# BT60.net
KiCad netlist of a schematic drawn in EAGLE
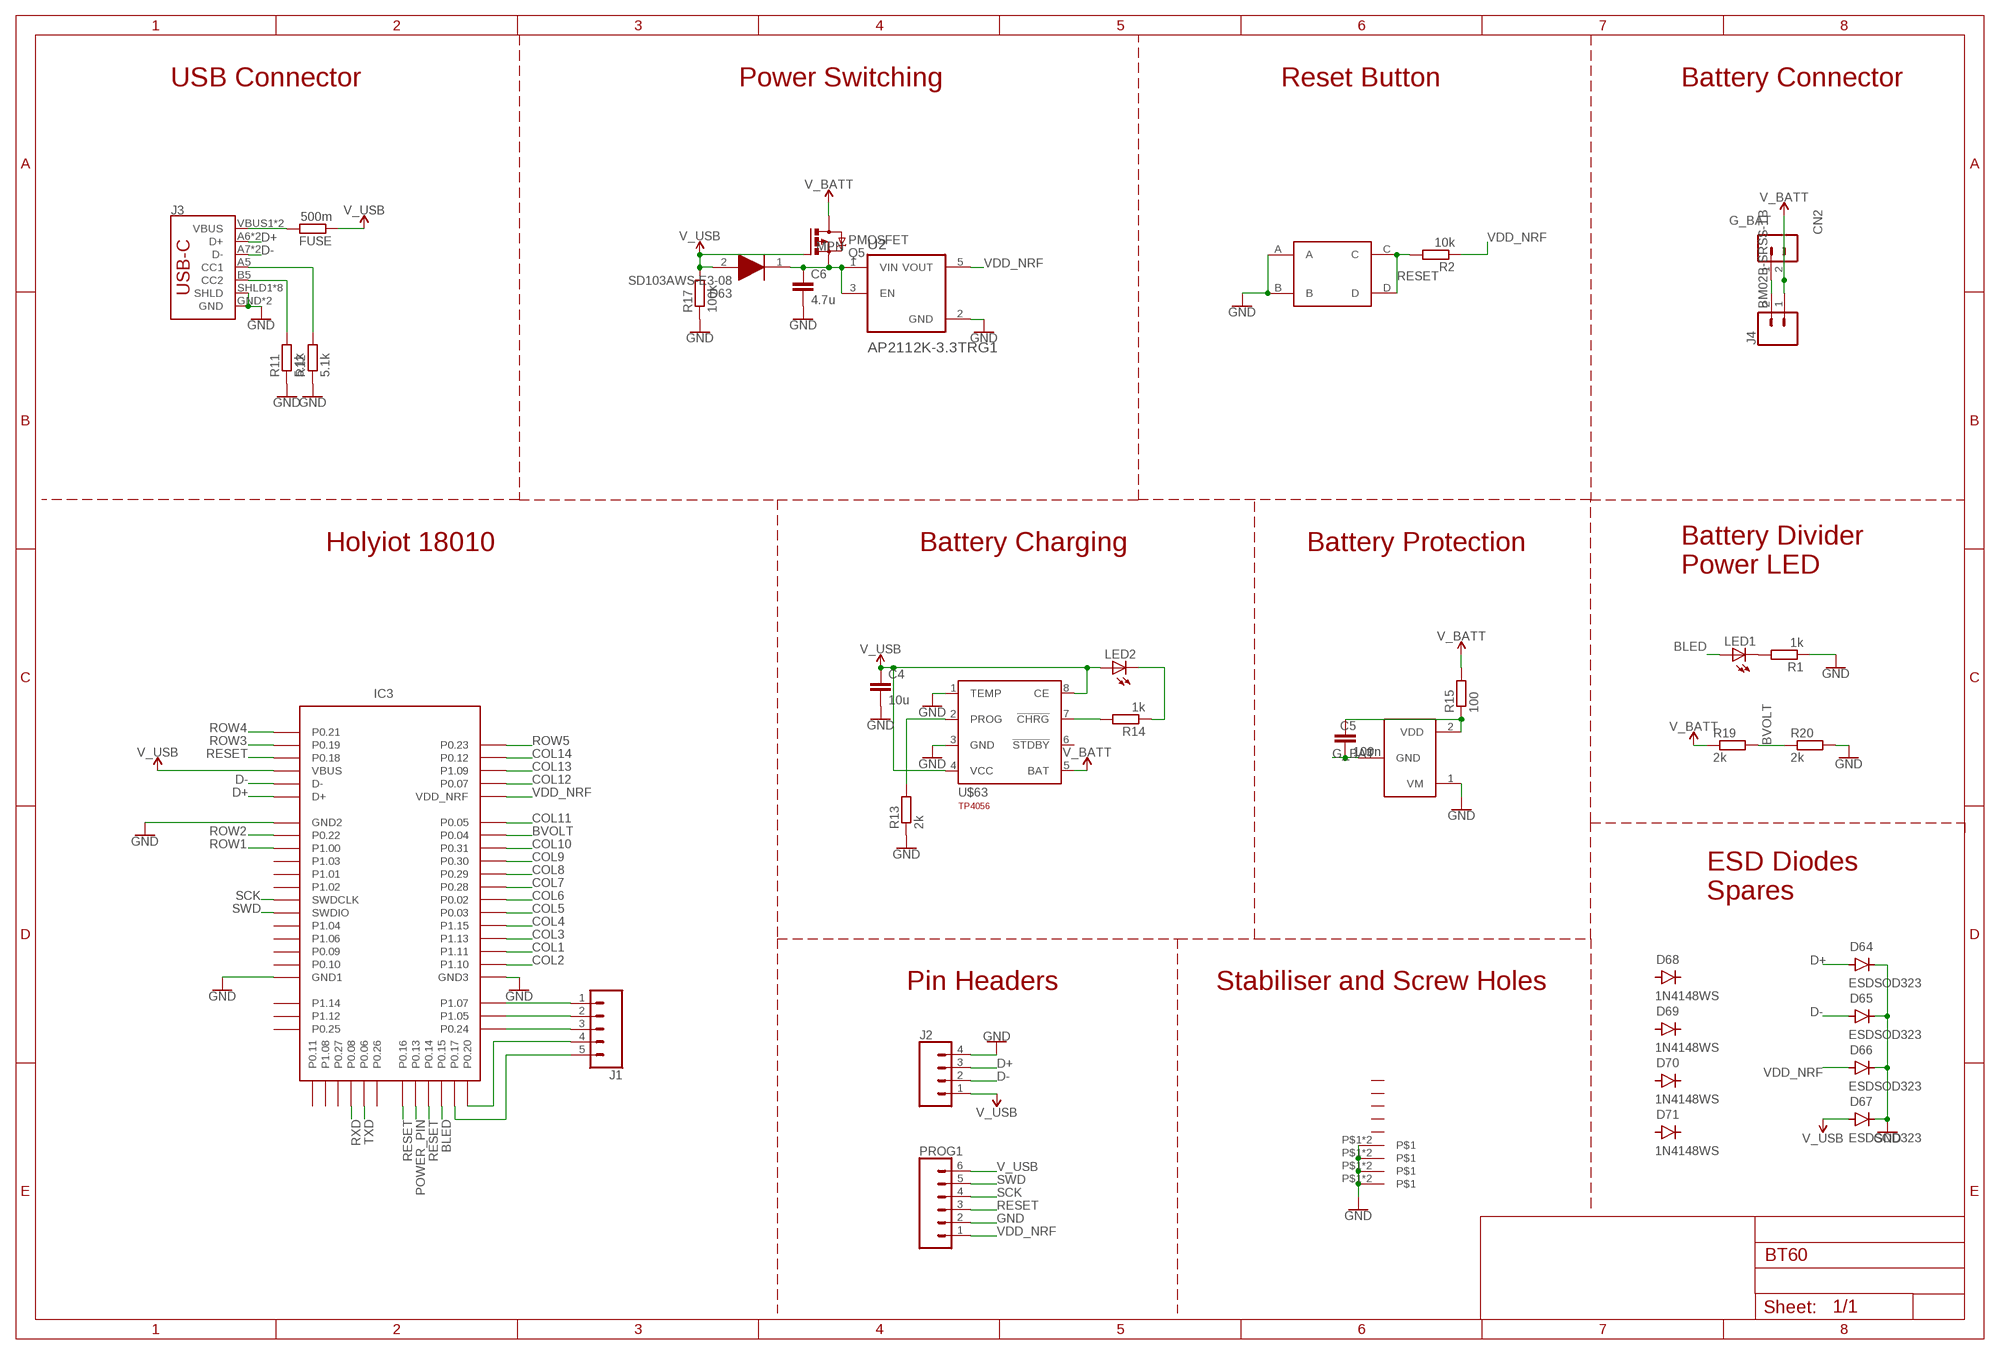
[diagram p0: schematic, sheet 1, part 1 of 2]
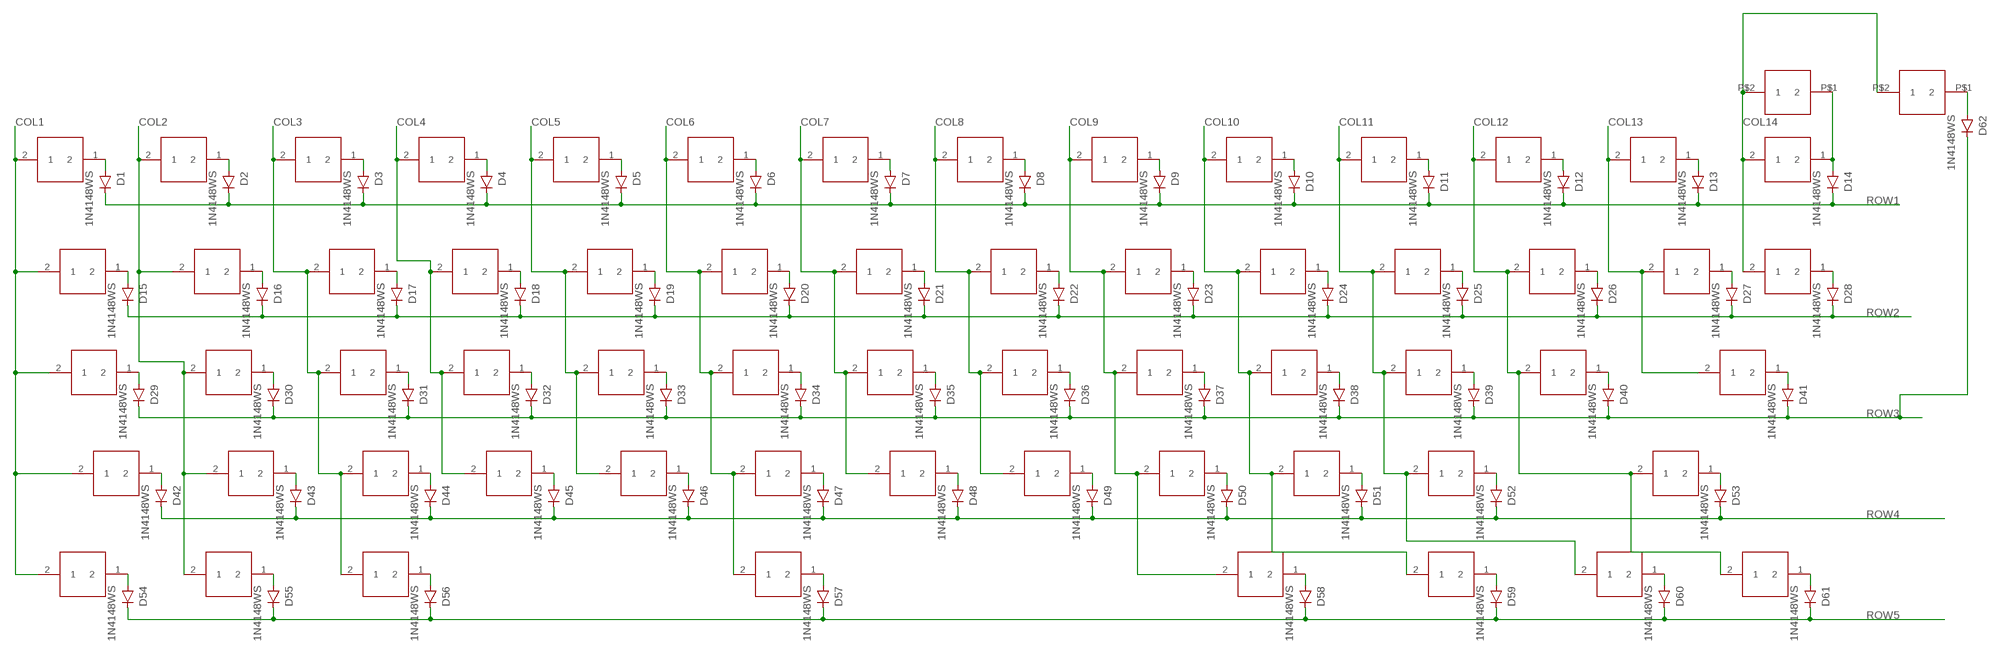
[diagram p1: schematic, sheet 1, part 2 of 2]

(export (version "E")
  (design (tool "Eeschema 10.0.6"))
  (components
    (comp (ref "C4")
      (value "10u")
      (footprint "eagle-import:C0603")
      (libsource (lib "eagle-import") (part "C-EUC0603"))
    )
    (comp (ref "C5")
      (value "100n")
      (footprint "eagle-import:C0603")
      (libsource (lib "eagle-import") (part "C-EUC0603"))
    )
    (comp (ref "C6")
      (value "4.7u")
      (footprint "eagle-import:C0603")
      (libsource (lib "eagle-import") (part "C-EUC0603"))
    )
    (comp (ref "CN2")
      (value "BM02B-SRSS-TB")
      (footprint "eagle-import:BM02B-SRSS-TB")
      (libsource (lib "eagle-import") (part "BM02B-SRSS-TB"))
    )
    (comp (ref "D1")
      (value "1N4148WS")
      (footprint "eagle-import:SOD-323")
      (fields
        (field (name "DIGIKEY_PART_NUMBER") "1N4148WSFSTR-ND")
        (field (name "MANUFACTURER") "Diodes Incorporated")
        (field (name "CREATED_BY") "PCBLayout.com")
      )
      (libsource (lib "eagle-import") (part "1N4148WS"))
    )
    (comp (ref "D2")
      (value "1N4148WS")
      (footprint "eagle-import:SOD-323")
      (fields
        (field (name "DIGIKEY_PART_NUMBER") "1N4148WSFSTR-ND")
        (field (name "MANUFACTURER") "Diodes Incorporated")
        (field (name "CREATED_BY") "PCBLayout.com")
      )
      (libsource (lib "eagle-import") (part "1N4148WS"))
    )
    (comp (ref "D3")
      (value "1N4148WS")
      (footprint "eagle-import:SOD-323")
      (fields
        (field (name "DIGIKEY_PART_NUMBER") "1N4148WSFSTR-ND")
        (field (name "MANUFACTURER") "Diodes Incorporated")
        (field (name "CREATED_BY") "PCBLayout.com")
      )
      (libsource (lib "eagle-import") (part "1N4148WS"))
    )
    (comp (ref "D4")
      (value "1N4148WS")
      (footprint "eagle-import:SOD-323")
      (fields
        (field (name "DIGIKEY_PART_NUMBER") "1N4148WSFSTR-ND")
        (field (name "MANUFACTURER") "Diodes Incorporated")
        (field (name "CREATED_BY") "PCBLayout.com")
      )
      (libsource (lib "eagle-import") (part "1N4148WS"))
    )
    (comp (ref "D5")
      (value "1N4148WS")
      (footprint "eagle-import:SOD-323")
      (fields
        (field (name "DIGIKEY_PART_NUMBER") "1N4148WSFSTR-ND")
        (field (name "MANUFACTURER") "Diodes Incorporated")
        (field (name "CREATED_BY") "PCBLayout.com")
      )
      (libsource (lib "eagle-import") (part "1N4148WS"))
    )
    (comp (ref "D6")
      (value "1N4148WS")
      (footprint "eagle-import:SOD-323")
      (fields
        (field (name "DIGIKEY_PART_NUMBER") "1N4148WSFSTR-ND")
        (field (name "MANUFACTURER") "Diodes Incorporated")
        (field (name "CREATED_BY") "PCBLayout.com")
      )
      (libsource (lib "eagle-import") (part "1N4148WS"))
    )
    (comp (ref "D7")
      (value "1N4148WS")
      (footprint "eagle-import:SOD-323")
      (fields
        (field (name "DIGIKEY_PART_NUMBER") "1N4148WSFSTR-ND")
        (field (name "MANUFACTURER") "Diodes Incorporated")
        (field (name "CREATED_BY") "PCBLayout.com")
      )
      (libsource (lib "eagle-import") (part "1N4148WS"))
    )
    (comp (ref "D8")
      (value "1N4148WS")
      (footprint "eagle-import:SOD-323")
      (fields
        (field (name "DIGIKEY_PART_NUMBER") "1N4148WSFSTR-ND")
        (field (name "MANUFACTURER") "Diodes Incorporated")
        (field (name "CREATED_BY") "PCBLayout.com")
      )
      (libsource (lib "eagle-import") (part "1N4148WS"))
    )
    (comp (ref "D9")
      (value "1N4148WS")
      (footprint "eagle-import:SOD-323")
      (fields
        (field (name "DIGIKEY_PART_NUMBER") "1N4148WSFSTR-ND")
        (field (name "MANUFACTURER") "Diodes Incorporated")
        (field (name "CREATED_BY") "PCBLayout.com")
      )
      (libsource (lib "eagle-import") (part "1N4148WS"))
    )
    (comp (ref "D10")
      (value "1N4148WS")
      (footprint "eagle-import:SOD-323")
      (fields
        (field (name "DIGIKEY_PART_NUMBER") "1N4148WSFSTR-ND")
        (field (name "MANUFACTURER") "Diodes Incorporated")
        (field (name "CREATED_BY") "PCBLayout.com")
      )
      (libsource (lib "eagle-import") (part "1N4148WS"))
    )
    (comp (ref "D11")
      (value "1N4148WS")
      (footprint "eagle-import:SOD-323")
      (fields
        (field (name "DIGIKEY_PART_NUMBER") "1N4148WSFSTR-ND")
        (field (name "MANUFACTURER") "Diodes Incorporated")
        (field (name "CREATED_BY") "PCBLayout.com")
      )
      (libsource (lib "eagle-import") (part "1N4148WS"))
    )
    (comp (ref "D12")
      (value "1N4148WS")
      (footprint "eagle-import:SOD-323")
      (fields
        (field (name "DIGIKEY_PART_NUMBER") "1N4148WSFSTR-ND")
        (field (name "MANUFACTURER") "Diodes Incorporated")
        (field (name "CREATED_BY") "PCBLayout.com")
      )
      (libsource (lib "eagle-import") (part "1N4148WS"))
    )
    (comp (ref "D13")
      (value "1N4148WS")
      (footprint "eagle-import:SOD-323")
      (fields
        (field (name "DIGIKEY_PART_NUMBER") "1N4148WSFSTR-ND")
        (field (name "MANUFACTURER") "Diodes Incorporated")
        (field (name "CREATED_BY") "PCBLayout.com")
      )
      (libsource (lib "eagle-import") (part "1N4148WS"))
    )
    (comp (ref "D14")
      (value "1N4148WS")
      (footprint "eagle-import:SOD-323")
      (fields
        (field (name "DIGIKEY_PART_NUMBER") "1N4148WSFSTR-ND")
        (field (name "MANUFACTURER") "Diodes Incorporated")
        (field (name "CREATED_BY") "PCBLayout.com")
      )
      (libsource (lib "eagle-import") (part "1N4148WS"))
    )
    (comp (ref "D15")
      (value "1N4148WS")
      (footprint "eagle-import:SOD-323")
      (fields
        (field (name "DIGIKEY_PART_NUMBER") "1N4148WSFSTR-ND")
        (field (name "MANUFACTURER") "Diodes Incorporated")
        (field (name "CREATED_BY") "PCBLayout.com")
      )
      (libsource (lib "eagle-import") (part "1N4148WS"))
    )
    (comp (ref "D16")
      (value "1N4148WS")
      (footprint "eagle-import:SOD-323")
      (fields
        (field (name "DIGIKEY_PART_NUMBER") "1N4148WSFSTR-ND")
        (field (name "MANUFACTURER") "Diodes Incorporated")
        (field (name "CREATED_BY") "PCBLayout.com")
      )
      (libsource (lib "eagle-import") (part "1N4148WS"))
    )
    (comp (ref "D17")
      (value "1N4148WS")
      (footprint "eagle-import:SOD-323")
      (fields
        (field (name "DIGIKEY_PART_NUMBER") "1N4148WSFSTR-ND")
        (field (name "MANUFACTURER") "Diodes Incorporated")
        (field (name "CREATED_BY") "PCBLayout.com")
      )
      (libsource (lib "eagle-import") (part "1N4148WS"))
    )
    (comp (ref "D18")
      (value "1N4148WS")
      (footprint "eagle-import:SOD-323")
      (fields
        (field (name "DIGIKEY_PART_NUMBER") "1N4148WSFSTR-ND")
        (field (name "MANUFACTURER") "Diodes Incorporated")
        (field (name "CREATED_BY") "PCBLayout.com")
      )
      (libsource (lib "eagle-import") (part "1N4148WS"))
    )
    (comp (ref "D19")
      (value "1N4148WS")
      (footprint "eagle-import:SOD-323")
      (fields
        (field (name "DIGIKEY_PART_NUMBER") "1N4148WSFSTR-ND")
        (field (name "MANUFACTURER") "Diodes Incorporated")
        (field (name "CREATED_BY") "PCBLayout.com")
      )
      (libsource (lib "eagle-import") (part "1N4148WS"))
    )
    (comp (ref "D20")
      (value "1N4148WS")
      (footprint "eagle-import:SOD-323")
      (fields
        (field (name "DIGIKEY_PART_NUMBER") "1N4148WSFSTR-ND")
        (field (name "MANUFACTURER") "Diodes Incorporated")
        (field (name "CREATED_BY") "PCBLayout.com")
      )
      (libsource (lib "eagle-import") (part "1N4148WS"))
    )
    (comp (ref "D21")
      (value "1N4148WS")
      (footprint "eagle-import:SOD-323")
      (fields
        (field (name "DIGIKEY_PART_NUMBER") "1N4148WSFSTR-ND")
        (field (name "MANUFACTURER") "Diodes Incorporated")
        (field (name "CREATED_BY") "PCBLayout.com")
      )
      (libsource (lib "eagle-import") (part "1N4148WS"))
    )
    (comp (ref "D22")
      (value "1N4148WS")
      (footprint "eagle-import:SOD-323")
      (fields
        (field (name "DIGIKEY_PART_NUMBER") "1N4148WSFSTR-ND")
        (field (name "MANUFACTURER") "Diodes Incorporated")
        (field (name "CREATED_BY") "PCBLayout.com")
      )
      (libsource (lib "eagle-import") (part "1N4148WS"))
    )
    (comp (ref "D23")
      (value "1N4148WS")
      (footprint "eagle-import:SOD-323")
      (fields
        (field (name "DIGIKEY_PART_NUMBER") "1N4148WSFSTR-ND")
        (field (name "MANUFACTURER") "Diodes Incorporated")
        (field (name "CREATED_BY") "PCBLayout.com")
      )
      (libsource (lib "eagle-import") (part "1N4148WS"))
    )
    (comp (ref "D24")
      (value "1N4148WS")
      (footprint "eagle-import:SOD-323")
      (fields
        (field (name "DIGIKEY_PART_NUMBER") "1N4148WSFSTR-ND")
        (field (name "MANUFACTURER") "Diodes Incorporated")
        (field (name "CREATED_BY") "PCBLayout.com")
      )
      (libsource (lib "eagle-import") (part "1N4148WS"))
    )
    (comp (ref "D25")
      (value "1N4148WS")
      (footprint "eagle-import:SOD-323")
      (fields
        (field (name "DIGIKEY_PART_NUMBER") "1N4148WSFSTR-ND")
        (field (name "MANUFACTURER") "Diodes Incorporated")
        (field (name "CREATED_BY") "PCBLayout.com")
      )
      (libsource (lib "eagle-import") (part "1N4148WS"))
    )
    (comp (ref "D26")
      (value "1N4148WS")
      (footprint "eagle-import:SOD-323")
      (fields
        (field (name "DIGIKEY_PART_NUMBER") "1N4148WSFSTR-ND")
        (field (name "MANUFACTURER") "Diodes Incorporated")
        (field (name "CREATED_BY") "PCBLayout.com")
      )
      (libsource (lib "eagle-import") (part "1N4148WS"))
    )
    (comp (ref "D27")
      (value "1N4148WS")
      (footprint "eagle-import:SOD-323")
      (fields
        (field (name "DIGIKEY_PART_NUMBER") "1N4148WSFSTR-ND")
        (field (name "MANUFACTURER") "Diodes Incorporated")
        (field (name "CREATED_BY") "PCBLayout.com")
      )
      (libsource (lib "eagle-import") (part "1N4148WS"))
    )
    (comp (ref "D28")
      (value "1N4148WS")
      (footprint "eagle-import:SOD-323")
      (fields
        (field (name "DIGIKEY_PART_NUMBER") "1N4148WSFSTR-ND")
        (field (name "MANUFACTURER") "Diodes Incorporated")
        (field (name "CREATED_BY") "PCBLayout.com")
      )
      (libsource (lib "eagle-import") (part "1N4148WS"))
    )
    (comp (ref "D29")
      (value "1N4148WS")
      (footprint "eagle-import:SOD-323")
      (fields
        (field (name "DIGIKEY_PART_NUMBER") "1N4148WSFSTR-ND")
        (field (name "MANUFACTURER") "Diodes Incorporated")
        (field (name "CREATED_BY") "PCBLayout.com")
      )
      (libsource (lib "eagle-import") (part "1N4148WS"))
    )
    (comp (ref "D30")
      (value "1N4148WS")
      (footprint "eagle-import:SOD-323")
      (fields
        (field (name "DIGIKEY_PART_NUMBER") "1N4148WSFSTR-ND")
        (field (name "MANUFACTURER") "Diodes Incorporated")
        (field (name "CREATED_BY") "PCBLayout.com")
      )
      (libsource (lib "eagle-import") (part "1N4148WS"))
    )
    (comp (ref "D31")
      (value "1N4148WS")
      (footprint "eagle-import:SOD-323")
      (fields
        (field (name "DIGIKEY_PART_NUMBER") "1N4148WSFSTR-ND")
        (field (name "MANUFACTURER") "Diodes Incorporated")
        (field (name "CREATED_BY") "PCBLayout.com")
      )
      (libsource (lib "eagle-import") (part "1N4148WS"))
    )
    (comp (ref "D32")
      (value "1N4148WS")
      (footprint "eagle-import:SOD-323")
      (fields
        (field (name "DIGIKEY_PART_NUMBER") "1N4148WSFSTR-ND")
        (field (name "MANUFACTURER") "Diodes Incorporated")
        (field (name "CREATED_BY") "PCBLayout.com")
      )
      (libsource (lib "eagle-import") (part "1N4148WS"))
    )
    (comp (ref "D33")
      (value "1N4148WS")
      (footprint "eagle-import:SOD-323")
      (fields
        (field (name "DIGIKEY_PART_NUMBER") "1N4148WSFSTR-ND")
        (field (name "MANUFACTURER") "Diodes Incorporated")
        (field (name "CREATED_BY") "PCBLayout.com")
      )
      (libsource (lib "eagle-import") (part "1N4148WS"))
    )
    (comp (ref "D34")
      (value "1N4148WS")
      (footprint "eagle-import:SOD-323")
      (fields
        (field (name "DIGIKEY_PART_NUMBER") "1N4148WSFSTR-ND")
        (field (name "MANUFACTURER") "Diodes Incorporated")
        (field (name "CREATED_BY") "PCBLayout.com")
      )
      (libsource (lib "eagle-import") (part "1N4148WS"))
    )
    (comp (ref "D35")
      (value "1N4148WS")
      (footprint "eagle-import:SOD-323")
      (fields
        (field (name "DIGIKEY_PART_NUMBER") "1N4148WSFSTR-ND")
        (field (name "MANUFACTURER") "Diodes Incorporated")
        (field (name "CREATED_BY") "PCBLayout.com")
      )
      (libsource (lib "eagle-import") (part "1N4148WS"))
    )
    (comp (ref "D36")
      (value "1N4148WS")
      (footprint "eagle-import:SOD-323")
      (fields
        (field (name "DIGIKEY_PART_NUMBER") "1N4148WSFSTR-ND")
        (field (name "MANUFACTURER") "Diodes Incorporated")
        (field (name "CREATED_BY") "PCBLayout.com")
      )
      (libsource (lib "eagle-import") (part "1N4148WS"))
    )
    (comp (ref "D37")
      (value "1N4148WS")
      (footprint "eagle-import:SOD-323")
      (fields
        (field (name "DIGIKEY_PART_NUMBER") "1N4148WSFSTR-ND")
        (field (name "MANUFACTURER") "Diodes Incorporated")
        (field (name "CREATED_BY") "PCBLayout.com")
      )
      (libsource (lib "eagle-import") (part "1N4148WS"))
    )
    (comp (ref "D38")
      (value "1N4148WS")
      (footprint "eagle-import:SOD-323")
      (fields
        (field (name "DIGIKEY_PART_NUMBER") "1N4148WSFSTR-ND")
        (field (name "MANUFACTURER") "Diodes Incorporated")
        (field (name "CREATED_BY") "PCBLayout.com")
      )
      (libsource (lib "eagle-import") (part "1N4148WS"))
    )
    (comp (ref "D39")
      (value "1N4148WS")
      (footprint "eagle-import:SOD-323")
      (fields
        (field (name "DIGIKEY_PART_NUMBER") "1N4148WSFSTR-ND")
        (field (name "MANUFACTURER") "Diodes Incorporated")
        (field (name "CREATED_BY") "PCBLayout.com")
      )
      (libsource (lib "eagle-import") (part "1N4148WS"))
    )
    (comp (ref "D40")
      (value "1N4148WS")
      (footprint "eagle-import:SOD-323")
      (fields
        (field (name "DIGIKEY_PART_NUMBER") "1N4148WSFSTR-ND")
        (field (name "MANUFACTURER") "Diodes Incorporated")
        (field (name "CREATED_BY") "PCBLayout.com")
      )
      (libsource (lib "eagle-import") (part "1N4148WS"))
    )
    (comp (ref "D41")
      (value "1N4148WS")
      (footprint "eagle-import:SOD-323")
      (fields
        (field (name "DIGIKEY_PART_NUMBER") "1N4148WSFSTR-ND")
        (field (name "MANUFACTURER") "Diodes Incorporated")
        (field (name "CREATED_BY") "PCBLayout.com")
      )
      (libsource (lib "eagle-import") (part "1N4148WS"))
    )
    (comp (ref "D42")
      (value "1N4148WS")
      (footprint "eagle-import:SOD-323")
      (fields
        (field (name "DIGIKEY_PART_NUMBER") "1N4148WSFSTR-ND")
        (field (name "MANUFACTURER") "Diodes Incorporated")
        (field (name "CREATED_BY") "PCBLayout.com")
      )
      (libsource (lib "eagle-import") (part "1N4148WS"))
    )
    (comp (ref "D43")
      (value "1N4148WS")
      (footprint "eagle-import:SOD-323")
      (fields
        (field (name "DIGIKEY_PART_NUMBER") "1N4148WSFSTR-ND")
        (field (name "MANUFACTURER") "Diodes Incorporated")
        (field (name "CREATED_BY") "PCBLayout.com")
      )
      (libsource (lib "eagle-import") (part "1N4148WS"))
    )
    (comp (ref "D44")
      (value "1N4148WS")
      (footprint "eagle-import:SOD-323")
      (fields
        (field (name "DIGIKEY_PART_NUMBER") "1N4148WSFSTR-ND")
        (field (name "MANUFACTURER") "Diodes Incorporated")
        (field (name "CREATED_BY") "PCBLayout.com")
      )
      (libsource (lib "eagle-import") (part "1N4148WS"))
    )
    (comp (ref "D45")
      (value "1N4148WS")
      (footprint "eagle-import:SOD-323")
      (fields
        (field (name "DIGIKEY_PART_NUMBER") "1N4148WSFSTR-ND")
        (field (name "MANUFACTURER") "Diodes Incorporated")
        (field (name "CREATED_BY") "PCBLayout.com")
      )
      (libsource (lib "eagle-import") (part "1N4148WS"))
    )
    (comp (ref "D46")
      (value "1N4148WS")
      (footprint "eagle-import:SOD-323")
      (fields
        (field (name "DIGIKEY_PART_NUMBER") "1N4148WSFSTR-ND")
        (field (name "MANUFACTURER") "Diodes Incorporated")
        (field (name "CREATED_BY") "PCBLayout.com")
      )
      (libsource (lib "eagle-import") (part "1N4148WS"))
    )
    (comp (ref "D47")
      (value "1N4148WS")
      (footprint "eagle-import:SOD-323")
      (fields
        (field (name "DIGIKEY_PART_NUMBER") "1N4148WSFSTR-ND")
        (field (name "MANUFACTURER") "Diodes Incorporated")
        (field (name "CREATED_BY") "PCBLayout.com")
      )
      (libsource (lib "eagle-import") (part "1N4148WS"))
    )
    (comp (ref "D48")
      (value "1N4148WS")
      (footprint "eagle-import:SOD-323")
      (fields
        (field (name "DIGIKEY_PART_NUMBER") "1N4148WSFSTR-ND")
        (field (name "MANUFACTURER") "Diodes Incorporated")
        (field (name "CREATED_BY") "PCBLayout.com")
      )
      (libsource (lib "eagle-import") (part "1N4148WS"))
    )
    (comp (ref "D49")
      (value "1N4148WS")
      (footprint "eagle-import:SOD-323")
      (fields
        (field (name "DIGIKEY_PART_NUMBER") "1N4148WSFSTR-ND")
        (field (name "MANUFACTURER") "Diodes Incorporated")
        (field (name "CREATED_BY") "PCBLayout.com")
      )
      (libsource (lib "eagle-import") (part "1N4148WS"))
    )
    (comp (ref "D50")
      (value "1N4148WS")
      (footprint "eagle-import:SOD-323")
      (fields
        (field (name "DIGIKEY_PART_NUMBER") "1N4148WSFSTR-ND")
        (field (name "MANUFACTURER") "Diodes Incorporated")
        (field (name "CREATED_BY") "PCBLayout.com")
      )
      (libsource (lib "eagle-import") (part "1N4148WS"))
    )
    (comp (ref "D51")
      (value "1N4148WS")
      (footprint "eagle-import:SOD-323")
      (fields
        (field (name "DIGIKEY_PART_NUMBER") "1N4148WSFSTR-ND")
        (field (name "MANUFACTURER") "Diodes Incorporated")
        (field (name "CREATED_BY") "PCBLayout.com")
      )
      (libsource (lib "eagle-import") (part "1N4148WS"))
    )
    (comp (ref "D52")
      (value "1N4148WS")
      (footprint "eagle-import:SOD-323")
      (fields
        (field (name "DIGIKEY_PART_NUMBER") "1N4148WSFSTR-ND")
        (field (name "MANUFACTURER") "Diodes Incorporated")
        (field (name "CREATED_BY") "PCBLayout.com")
      )
      (libsource (lib "eagle-import") (part "1N4148WS"))
    )
    (comp (ref "D53")
      (value "1N4148WS")
      (footprint "eagle-import:SOD-323")
      (fields
        (field (name "DIGIKEY_PART_NUMBER") "1N4148WSFSTR-ND")
        (field (name "MANUFACTURER") "Diodes Incorporated")
        (field (name "CREATED_BY") "PCBLayout.com")
      )
      (libsource (lib "eagle-import") (part "1N4148WS"))
    )
    (comp (ref "D54")
      (value "1N4148WS")
      (footprint "eagle-import:SOD-323")
      (fields
        (field (name "DIGIKEY_PART_NUMBER") "1N4148WSFSTR-ND")
        (field (name "MANUFACTURER") "Diodes Incorporated")
        (field (name "CREATED_BY") "PCBLayout.com")
      )
      (libsource (lib "eagle-import") (part "1N4148WS"))
    )
    (comp (ref "D55")
      (value "1N4148WS")
      (footprint "eagle-import:SOD-323")
      (fields
        (field (name "DIGIKEY_PART_NUMBER") "1N4148WSFSTR-ND")
        (field (name "MANUFACTURER") "Diodes Incorporated")
        (field (name "CREATED_BY") "PCBLayout.com")
      )
      (libsource (lib "eagle-import") (part "1N4148WS"))
    )
    (comp (ref "D56")
      (value "1N4148WS")
      (footprint "eagle-import:SOD-323")
      (fields
        (field (name "DIGIKEY_PART_NUMBER") "1N4148WSFSTR-ND")
        (field (name "MANUFACTURER") "Diodes Incorporated")
        (field (name "CREATED_BY") "PCBLayout.com")
      )
      (libsource (lib "eagle-import") (part "1N4148WS"))
    )
    (comp (ref "D57")
      (value "1N4148WS")
      (footprint "eagle-import:SOD-323")
      (fields
        (field (name "DIGIKEY_PART_NUMBER") "1N4148WSFSTR-ND")
        (field (name "MANUFACTURER") "Diodes Incorporated")
        (field (name "CREATED_BY") "PCBLayout.com")
      )
      (libsource (lib "eagle-import") (part "1N4148WS"))
    )
    (comp (ref "D58")
      (value "1N4148WS")
      (footprint "eagle-import:SOD-323")
      (fields
        (field (name "DIGIKEY_PART_NUMBER") "1N4148WSFSTR-ND")
        (field (name "MANUFACTURER") "Diodes Incorporated")
        (field (name "CREATED_BY") "PCBLayout.com")
      )
      (libsource (lib "eagle-import") (part "1N4148WS"))
    )
    (comp (ref "D59")
      (value "1N4148WS")
      (footprint "eagle-import:SOD-323")
      (fields
        (field (name "DIGIKEY_PART_NUMBER") "1N4148WSFSTR-ND")
        (field (name "MANUFACTURER") "Diodes Incorporated")
        (field (name "CREATED_BY") "PCBLayout.com")
      )
      (libsource (lib "eagle-import") (part "1N4148WS"))
    )
    (comp (ref "D60")
      (value "1N4148WS")
      (footprint "eagle-import:SOD-323")
      (fields
        (field (name "DIGIKEY_PART_NUMBER") "1N4148WSFSTR-ND")
        (field (name "MANUFACTURER") "Diodes Incorporated")
        (field (name "CREATED_BY") "PCBLayout.com")
      )
      (libsource (lib "eagle-import") (part "1N4148WS"))
    )
    (comp (ref "D61")
      (value "1N4148WS")
      (footprint "eagle-import:SOD-323")
      (fields
        (field (name "DIGIKEY_PART_NUMBER") "1N4148WSFSTR-ND")
        (field (name "MANUFACTURER") "Diodes Incorporated")
        (field (name "CREATED_BY") "PCBLayout.com")
      )
      (libsource (lib "eagle-import") (part "1N4148WS"))
    )
    (comp (ref "D62")
      (value "1N4148WS")
      (footprint "eagle-import:SOD-323")
      (fields
        (field (name "DIGIKEY_PART_NUMBER") "1N4148WSFSTR-ND")
        (field (name "MANUFACTURER") "Diodes Incorporated")
        (field (name "CREATED_BY") "PCBLayout.com")
      )
      (libsource (lib "eagle-import") (part "1N4148WS"))
    )
    (comp (ref "D63")
      (value "SD103AWS-E3-08")
      (footprint "eagle-import:SOD2713X115N")
      (fields (field (name "MOUSER_PART_NUMBER") "78-SD103AWS-E3-08"))
      (libsource (lib "eagle-import") (part "SD103AWS-E3-08"))
    )
    (comp (ref "D64")
      (value "ESDSOD323")
      (footprint "eagle-import:SOD-323")
      (fields (field (name "MANUFACTURER") "Diodes Incorporated") (field (name "CREATED_BY") "PCBLayout.com"))
      (libsource (lib "eagle-import") (part "ESDSOD323"))
    )
    (comp (ref "D65")
      (value "ESDSOD323")
      (footprint "eagle-import:SOD-323")
      (fields (field (name "MANUFACTURER") "Diodes Incorporated") (field (name "CREATED_BY") "PCBLayout.com"))
      (libsource (lib "eagle-import") (part "ESDSOD323"))
    )
    (comp (ref "D66")
      (value "ESDSOD323")
      (footprint "eagle-import:SOD-323")
      (fields (field (name "MANUFACTURER") "Diodes Incorporated") (field (name "CREATED_BY") "PCBLayout.com"))
      (libsource (lib "eagle-import") (part "ESDSOD323"))
    )
    (comp (ref "D67")
      (value "ESDSOD323")
      (footprint "eagle-import:SOD-323")
      (fields (field (name "MANUFACTURER") "Diodes Incorporated") (field (name "CREATED_BY") "PCBLayout.com"))
      (libsource (lib "eagle-import") (part "ESDSOD323"))
    )
    (comp (ref "D68")
      (value "1N4148WS")
      (footprint "eagle-import:SOD-323")
      (fields
        (field (name "DIGIKEY_PART_NUMBER") "1N4148WSFSTR-ND")
        (field (name "MANUFACTURER") "Diodes Incorporated")
        (field (name "CREATED_BY") "PCBLayout.com")
      )
      (libsource (lib "eagle-import") (part "1N4148WS"))
    )
    (comp (ref "D69")
      (value "1N4148WS")
      (footprint "eagle-import:SOD-323")
      (fields
        (field (name "DIGIKEY_PART_NUMBER") "1N4148WSFSTR-ND")
        (field (name "MANUFACTURER") "Diodes Incorporated")
        (field (name "CREATED_BY") "PCBLayout.com")
      )
      (libsource (lib "eagle-import") (part "1N4148WS"))
    )
    (comp (ref "D70")
      (value "1N4148WS")
      (footprint "eagle-import:SOD-323")
      (fields
        (field (name "DIGIKEY_PART_NUMBER") "1N4148WSFSTR-ND")
        (field (name "MANUFACTURER") "Diodes Incorporated")
        (field (name "CREATED_BY") "PCBLayout.com")
      )
      (libsource (lib "eagle-import") (part "1N4148WS"))
    )
    (comp (ref "D71")
      (value "1N4148WS")
      (footprint "eagle-import:SOD-323")
      (fields
        (field (name "DIGIKEY_PART_NUMBER") "1N4148WSFSTR-ND")
        (field (name "MANUFACTURER") "Diodes Incorporated")
        (field (name "CREATED_BY") "PCBLayout.com")
      )
      (libsource (lib "eagle-import") (part "1N4148WS"))
    )
    (comp (ref "FUSE")
      (value "500m")
      (footprint "eagle-import:R0603")
      (libsource (lib "eagle-import") (part "R-EU_R0603"))
    )
    (comp (ref "IC1")
      (value "XB3303ASOT23")
      (footprint "eagle-import:SOT23-3")
      (libsource (lib "eagle-import") (part "XB3303ASOT23"))
    )
    (comp (ref "IC3")
      (value "HOLYIOT_18010")
      (footprint "eagle-import:PCBCOMPONENT_1")
      (libsource (lib "eagle-import") (part "HOLYIOT_18010"))
    )
    (comp (ref "J1")
      (value "CONN_051.27MM")
      (footprint "eagle-import:1X05_1.27MM")
      (libsource (lib "eagle-import") (part "CONN_051.27MM"))
    )
    (comp (ref "J2")
      (value "CONN_041X04_NO_SILK")
      (footprint "eagle-import:1X04_NO_SILK")
      (libsource (lib "eagle-import") (part "CONN_041X04_NO_SILK"))
    )
    (comp (ref "J3")
      (value "SPARKFUN-CONNECTORS_USB_C16PIN")
      (footprint "eagle-import:SPARKFUN-CONNECTORS_USB-C-16P")
      (libsource (lib "eagle-import") (part "SPARKFUN-CONNECTORS_USB_C16PIN"))
    )
    (comp (ref "J4")
      (value "CONN_02")
      (footprint "eagle-import:1X02")
      (libsource (lib "eagle-import") (part "CONN_02"))
    )
    (comp (ref "LED1")
      (value "LEDCHIPLED_0805")
      (footprint "eagle-import:CHIPLED_0805")
      (libsource (lib "eagle-import") (part "LEDCHIPLED_0805"))
    )
    (comp (ref "LED2")
      (value "LEDCHIPLED_0805")
      (footprint "eagle-import:CHIPLED_0805")
      (libsource (lib "eagle-import") (part "LEDCHIPLED_0805"))
    )
    (comp (ref "PROG1")
      (value "CONN_06NO_SILK_FEMALE_PTH")
      (footprint "eagle-import:1X06_NO_SILK")
      (libsource (lib "eagle-import") (part "CONN_06NO_SILK_FEMALE_PTH"))
    )
    (comp (ref "Q5")
      (value "PMOSFET")
      (footprint "eagle-import:SOT23")
      (fields (field (name "MPN") "SL2301S"))
      (libsource (lib "eagle-import") (part "PMOSFETSOT23_"))
    )
    (comp (ref "R1")
      (value "1k")
      (footprint "eagle-import:R0603")
      (libsource (lib "eagle-import") (part "R-EU_R0603"))
    )
    (comp (ref "R2")
      (value "10k")
      (footprint "eagle-import:R0603")
      (libsource (lib "eagle-import") (part "R-EU_R0603"))
    )
    (comp (ref "R11")
      (value "5.1k")
      (footprint "eagle-import:R0603")
      (libsource (lib "eagle-import") (part "R-EU_R0603"))
    )
    (comp (ref "R12")
      (value "5.1k")
      (footprint "eagle-import:R0603")
      (libsource (lib "eagle-import") (part "R-EU_R0603"))
    )
    (comp (ref "R13")
      (value "2k")
      (footprint "eagle-import:R0603")
      (libsource (lib "eagle-import") (part "R-EU_R0603"))
    )
    (comp (ref "R14")
      (value "1k")
      (footprint "eagle-import:R0603")
      (libsource (lib "eagle-import") (part "R-EU_R0603"))
    )
    (comp (ref "R15")
      (value "100")
      (footprint "eagle-import:R0603")
      (libsource (lib "eagle-import") (part "R-EU_R0603"))
    )
    (comp (ref "R17")
      (value "100k")
      (footprint "eagle-import:R0603")
      (libsource (lib "eagle-import") (part "R-EU_R0603"))
    )
    (comp (ref "R19")
      (value "2k")
      (footprint "eagle-import:R0603")
      (libsource (lib "eagle-import") (part "R-EU_R0603"))
    )
    (comp (ref "R20")
      (value "2k")
      (footprint "eagle-import:R0603")
      (libsource (lib "eagle-import") (part "R-EU_R0603"))
    )
    (comp (ref "U$1")
      (value "CHERRY")
      (footprint "eagle-import:CHERRY")
      (libsource (lib "eagle-import") (part "CHERRY"))
    )
    (comp (ref "U$2")
      (value "CHERRY")
      (footprint "eagle-import:CHERRY")
      (libsource (lib "eagle-import") (part "CHERRY"))
    )
    (comp (ref "U$3")
      (value "CHERRY")
      (footprint "eagle-import:CHERRY")
      (libsource (lib "eagle-import") (part "CHERRY"))
    )
    (comp (ref "U$4")
      (value "CHERRY")
      (footprint "eagle-import:CHERRY")
      (libsource (lib "eagle-import") (part "CHERRY"))
    )
    (comp (ref "U$5")
      (value "CHERRY")
      (footprint "eagle-import:CHERRY")
      (libsource (lib "eagle-import") (part "CHERRY"))
    )
    (comp (ref "U$6")
      (value "CHERRY")
      (footprint "eagle-import:CHERRY")
      (libsource (lib "eagle-import") (part "CHERRY"))
    )
    (comp (ref "U$7")
      (value "CHERRY")
      (footprint "eagle-import:CHERRY")
      (libsource (lib "eagle-import") (part "CHERRY"))
    )
    (comp (ref "U$8")
      (value "CHERRY")
      (footprint "eagle-import:CHERRY")
      (libsource (lib "eagle-import") (part "CHERRY"))
    )
    (comp (ref "U$9")
      (value "CHERRY")
      (footprint "eagle-import:CHERRY")
      (libsource (lib "eagle-import") (part "CHERRY"))
    )
    (comp (ref "U$10")
      (value "CHERRY")
      (footprint "eagle-import:CHERRY")
      (libsource (lib "eagle-import") (part "CHERRY"))
    )
    (comp (ref "U$11")
      (value "CHERRY")
      (footprint "eagle-import:CHERRY")
      (libsource (lib "eagle-import") (part "CHERRY"))
    )
    (comp (ref "U$12")
      (value "CHERRY")
      (footprint "eagle-import:CHERRY")
      (libsource (lib "eagle-import") (part "CHERRY"))
    )
    (comp (ref "U$13")
      (value "CHERRY")
      (footprint "eagle-import:CHERRY")
      (libsource (lib "eagle-import") (part "CHERRY"))
    )
    (comp (ref "U$14")
      (value "CHERRY_CORNER_OFFED")
      (footprint "eagle-import:CHERRY_CORNER_OFFED")
      (libsource (lib "eagle-import") (part "CHERRY_CORNER_OFFED"))
    )
    (comp (ref "U$15")
      (value "CHERRY")
      (footprint "eagle-import:CHERRY")
      (libsource (lib "eagle-import") (part "CHERRY"))
    )
    (comp (ref "U$16")
      (value "CHERRY")
      (footprint "eagle-import:CHERRY")
      (libsource (lib "eagle-import") (part "CHERRY"))
    )
    (comp (ref "U$17")
      (value "CHERRY")
      (footprint "eagle-import:CHERRY")
      (libsource (lib "eagle-import") (part "CHERRY"))
    )
    (comp (ref "U$18")
      (value "CHERRY")
      (footprint "eagle-import:CHERRY")
      (libsource (lib "eagle-import") (part "CHERRY"))
    )
    (comp (ref "U$19")
      (value "CHERRY")
      (footprint "eagle-import:CHERRY")
      (libsource (lib "eagle-import") (part "CHERRY"))
    )
    (comp (ref "U$20")
      (value "CHERRY")
      (footprint "eagle-import:CHERRY")
      (libsource (lib "eagle-import") (part "CHERRY"))
    )
    (comp (ref "U$21")
      (value "CHERRY")
      (footprint "eagle-import:CHERRY")
      (libsource (lib "eagle-import") (part "CHERRY"))
    )
    (comp (ref "U$22")
      (value "CHERRY")
      (footprint "eagle-import:CHERRY")
      (libsource (lib "eagle-import") (part "CHERRY"))
    )
    (comp (ref "U$23")
      (value "CHERRY")
      (footprint "eagle-import:CHERRY")
      (libsource (lib "eagle-import") (part "CHERRY"))
    )
    (comp (ref "U$24")
      (value "CHERRY")
      (footprint "eagle-import:CHERRY")
      (libsource (lib "eagle-import") (part "CHERRY"))
    )
    (comp (ref "U$25")
      (value "CHERRY")
      (footprint "eagle-import:CHERRY")
      (libsource (lib "eagle-import") (part "CHERRY"))
    )
    (comp (ref "U$26")
      (value "CHERRY")
      (footprint "eagle-import:CHERRY")
      (libsource (lib "eagle-import") (part "CHERRY"))
    )
    (comp (ref "U$27")
      (value "CHERRY")
      (footprint "eagle-import:CHERRY")
      (libsource (lib "eagle-import") (part "CHERRY"))
    )
    (comp (ref "U$28")
      (value "CHERRY_CORNER_OFFED")
      (footprint "eagle-import:CHERRY_CORNER_OFFED")
      (libsource (lib "eagle-import") (part "CHERRY_CORNER_OFFED"))
    )
    (comp (ref "U$29")
      (value "CHERRY")
      (footprint "eagle-import:CHERRY")
      (libsource (lib "eagle-import") (part "CHERRY"))
    )
    (comp (ref "U$30")
      (value "CHERRY")
      (footprint "eagle-import:CHERRY")
      (libsource (lib "eagle-import") (part "CHERRY"))
    )
    (comp (ref "U$31")
      (value "CHERRY")
      (footprint "eagle-import:CHERRY")
      (libsource (lib "eagle-import") (part "CHERRY"))
    )
    (comp (ref "U$32")
      (value "CHERRY")
      (footprint "eagle-import:CHERRY")
      (libsource (lib "eagle-import") (part "CHERRY"))
    )
    (comp (ref "U$33")
      (value "CHERRY")
      (footprint "eagle-import:CHERRY")
      (libsource (lib "eagle-import") (part "CHERRY"))
    )
    (comp (ref "U$34")
      (value "CHERRY")
      (footprint "eagle-import:CHERRY")
      (libsource (lib "eagle-import") (part "CHERRY"))
    )
    (comp (ref "U$35")
      (value "CHERRY_CORNER_OFFED")
      (footprint "eagle-import:CHERRY_CORNER_OFFED")
      (libsource (lib "eagle-import") (part "CHERRY_CORNER_OFFED"))
    )
    (comp (ref "U$36")
      (value "CHERRY")
      (footprint "eagle-import:CHERRY")
      (libsource (lib "eagle-import") (part "CHERRY"))
    )
    (comp (ref "U$37")
      (value "CHERRY")
      (footprint "eagle-import:CHERRY")
      (libsource (lib "eagle-import") (part "CHERRY"))
    )
    (comp (ref "U$38")
      (value "CHERRY")
      (footprint "eagle-import:CHERRY")
      (libsource (lib "eagle-import") (part "CHERRY"))
    )
    (comp (ref "U$39")
      (value "CHERRY")
      (footprint "eagle-import:CHERRY")
      (libsource (lib "eagle-import") (part "CHERRY"))
    )
    (comp (ref "U$40")
      (value "CHERRY")
      (footprint "eagle-import:CHERRY")
      (libsource (lib "eagle-import") (part "CHERRY"))
    )
    (comp (ref "U$41")
      (value "CHERRY")
      (footprint "eagle-import:CHERRY")
      (libsource (lib "eagle-import") (part "CHERRY"))
    )
    (comp (ref "U$42")
      (value "CHERRY")
      (footprint "eagle-import:CHERRY")
      (libsource (lib "eagle-import") (part "CHERRY"))
    )
    (comp (ref "U$43")
      (value "CHERRY")
      (footprint "eagle-import:CHERRY")
      (libsource (lib "eagle-import") (part "CHERRY"))
    )
    (comp (ref "U$44")
      (value "CHERRY")
      (footprint "eagle-import:CHERRY")
      (libsource (lib "eagle-import") (part "CHERRY"))
    )
    (comp (ref "U$45")
      (value "CHERRY")
      (footprint "eagle-import:CHERRY")
      (libsource (lib "eagle-import") (part "CHERRY"))
    )
    (comp (ref "U$46")
      (value "CHERRY")
      (footprint "eagle-import:CHERRY")
      (libsource (lib "eagle-import") (part "CHERRY"))
    )
    (comp (ref "U$47")
      (value "CHERRY")
      (footprint "eagle-import:CHERRY")
      (libsource (lib "eagle-import") (part "CHERRY"))
    )
    (comp (ref "U$48")
      (value "CHERRY")
      (footprint "eagle-import:CHERRY")
      (libsource (lib "eagle-import") (part "CHERRY"))
    )
    (comp (ref "U$49")
      (value "CHERRY")
      (footprint "eagle-import:CHERRY")
      (libsource (lib "eagle-import") (part "CHERRY"))
    )
    (comp (ref "U$50")
      (value "CHERRY")
      (footprint "eagle-import:CHERRY")
      (libsource (lib "eagle-import") (part "CHERRY"))
    )
    (comp (ref "U$51")
      (value "CHERRY")
      (footprint "eagle-import:CHERRY")
      (libsource (lib "eagle-import") (part "CHERRY"))
    )
    (comp (ref "U$52")
      (value "CHERRY")
      (footprint "eagle-import:CHERRY")
      (libsource (lib "eagle-import") (part "CHERRY"))
    )
    (comp (ref "U$53")
      (value "CHERRY")
      (footprint "eagle-import:CHERRY")
      (libsource (lib "eagle-import") (part "CHERRY"))
    )
    (comp (ref "U$54")
      (value "CHERRY")
      (footprint "eagle-import:CHERRY")
      (libsource (lib "eagle-import") (part "CHERRY"))
    )
    (comp (ref "U$55")
      (value "CHERRY")
      (footprint "eagle-import:CHERRY")
      (libsource (lib "eagle-import") (part "CHERRY"))
    )
    (comp (ref "U$56")
      (value "CHERRY")
      (footprint "eagle-import:CHERRY")
      (libsource (lib "eagle-import") (part "CHERRY"))
    )
    (comp (ref "U$57")
      (value "CHERRY")
      (footprint "eagle-import:CHERRY")
      (libsource (lib "eagle-import") (part "CHERRY"))
    )
    (comp (ref "U$58")
      (value "CHERRY")
      (footprint "eagle-import:CHERRY")
      (libsource (lib "eagle-import") (part "CHERRY"))
    )
    (comp (ref "U$59")
      (value "CHERRY")
      (footprint "eagle-import:CHERRY")
      (libsource (lib "eagle-import") (part "CHERRY"))
    )
    (comp (ref "U$60")
      (value "CHERRY")
      (footprint "eagle-import:CHERRY")
      (libsource (lib "eagle-import") (part "CHERRY"))
    )
    (comp (ref "U$61")
      (value "CHERRY")
      (footprint "eagle-import:CHERRY")
      (libsource (lib "eagle-import") (part "CHERRY"))
    )
    (comp (ref "U$62")
      (value "SMD-BUTTON")
      (footprint "eagle-import:SMD-BUTTON")
      (libsource (lib "eagle-import") (part "SMD-BUTTON"))
    )
    (comp (ref "U$63")
      (value "TP4056SOI8")
      (footprint "eagle-import:SOIC8")
      (libsource (lib "eagle-import") (part "TP4056SOI8"))
    )
    (comp (ref "U$64")
      (value "2.5MM_ELONGATED")
      (footprint "eagle-import:2.5MM_ELONGATED")
      (libsource (lib "eagle-import") (part "2.5MM_ELONGATED"))
    )
    (comp (ref "U$65")
      (value "2.5MM_ELONGATED")
      (footprint "eagle-import:2.5MM_ELONGATED")
      (libsource (lib "eagle-import") (part "2.5MM_ELONGATED"))
    )
    (comp (ref "U$66")
      (value "2.5MM_HOLE")
      (footprint "eagle-import:2.5MM_HOLE")
      (libsource (lib "eagle-import") (part "2.5MM_HOLE"))
    )
    (comp (ref "U$67")
      (value "2.5MM_ELONGATED")
      (footprint "eagle-import:2.5MM_ELONGATED")
      (libsource (lib "eagle-import") (part "2.5MM_ELONGATED"))
    )
    (comp (ref "U$68")
      (value "STAB-2U")
      (footprint "eagle-import:STAB-2U")
      (libsource (lib "eagle-import") (part "STAB-2U"))
    )
    (comp (ref "U$69")
      (value "STAB-2U")
      (footprint "eagle-import:STAB-2U")
      (libsource (lib "eagle-import") (part "STAB-2U"))
    )
    (comp (ref "U$70")
      (value "STAB-2U")
      (footprint "eagle-import:STAB-2U")
      (libsource (lib "eagle-import") (part "STAB-2U"))
    )
    (comp (ref "U$71")
      (value "STAB-2U")
      (footprint "eagle-import:STAB-2U")
      (libsource (lib "eagle-import") (part "STAB-2U"))
    )
    (comp (ref "U$72")
      (value "STAB-6U")
      (footprint "eagle-import:STAB-6.25U")
      (libsource (lib "eagle-import") (part "STAB-6U"))
    )
    (comp (ref "U$73")
      (value "CHERRY-SOLDER")
      (footprint "eagle-import:CHERRY-SOLDER")
      (libsource (lib "eagle-import") (part "CHERRY-SOLDER"))
    )
    (comp (ref "U$74")
      (value "CHERRY-SOLDER")
      (footprint "eagle-import:CHERRY-SOLDER")
      (libsource (lib "eagle-import") (part "CHERRY-SOLDER"))
    )
    (comp (ref "U2")
      (value "AP2112K-3.3TRG1")
      (footprint "eagle-import:SOT95P285X140-5N")
      (fields (field (name "MF") "Diodes Inc."))
      (libsource (lib "eagle-import") (part "AP2112K-3.3TRG1"))
    )
  )
  (nets
    (net (code "1") (name "/BLED") (class "Default")
      (node (ref "IC3") (pin "P0.15") (pinfunction "P0.15_P0.15") (pintype "bidirectional"))
      (node (ref "LED1") (pin "A") (pinfunction "A_A") (pintype "passive"))
    )
    (net (code "2") (name "/BVOLT") (class "Default")
      (node (ref "IC3") (pin "P0.04") (pinfunction "P0.04_P0.04") (pintype "bidirectional"))
      (node (ref "R19") (pin "2") (pinfunction "2_2") (pintype "passive"))
      (node (ref "R20") (pin "1") (pinfunction "1_1") (pintype "passive"))
    )
    (net (code "3") (name "/COL1") (class "Default")
      (node (ref "IC3") (pin "P1.11") (pinfunction "P1.11_P1.11") (pintype "bidirectional"))
      (node (ref "U$1") (pin "2") (pinfunction "1_2") (pintype "bidirectional"))
      (node (ref "U$15") (pin "2") (pinfunction "1_2") (pintype "bidirectional"))
      (node (ref "U$29") (pin "2") (pinfunction "1_2") (pintype "bidirectional"))
      (node (ref "U$42") (pin "2") (pinfunction "1_2") (pintype "bidirectional"))
      (node (ref "U$54") (pin "2") (pinfunction "1_2") (pintype "bidirectional"))
    )
    (net (code "4") (name "/COL2") (class "Default")
      (node (ref "IC3") (pin "P1.10") (pinfunction "P1.10_P1.10") (pintype "bidirectional"))
      (node (ref "U$16") (pin "2") (pinfunction "1_2") (pintype "bidirectional"))
      (node (ref "U$2") (pin "2") (pinfunction "1_2") (pintype "bidirectional"))
      (node (ref "U$30") (pin "2") (pinfunction "1_2") (pintype "bidirectional"))
      (node (ref "U$43") (pin "2") (pinfunction "1_2") (pintype "bidirectional"))
      (node (ref "U$55") (pin "2") (pinfunction "1_2") (pintype "bidirectional"))
    )
    (net (code "5") (name "/COL3") (class "Default")
      (node (ref "IC3") (pin "P1.13") (pinfunction "P1.13_P1.13") (pintype "bidirectional"))
      (node (ref "U$17") (pin "2") (pinfunction "1_2") (pintype "bidirectional"))
      (node (ref "U$3") (pin "2") (pinfunction "1_2") (pintype "bidirectional"))
      (node (ref "U$31") (pin "2") (pinfunction "1_2") (pintype "bidirectional"))
      (node (ref "U$44") (pin "2") (pinfunction "1_2") (pintype "bidirectional"))
      (node (ref "U$56") (pin "2") (pinfunction "1_2") (pintype "bidirectional"))
    )
    (net (code "6") (name "/COL4") (class "Default")
      (node (ref "IC3") (pin "P1.15") (pinfunction "P1.15_P1.15") (pintype "bidirectional"))
      (node (ref "U$18") (pin "2") (pinfunction "1_2") (pintype "bidirectional"))
      (node (ref "U$32") (pin "2") (pinfunction "1_2") (pintype "bidirectional"))
      (node (ref "U$4") (pin "2") (pinfunction "1_2") (pintype "bidirectional"))
      (node (ref "U$45") (pin "2") (pinfunction "1_2") (pintype "bidirectional"))
    )
    (net (code "7") (name "/COL5") (class "Default")
      (node (ref "IC3") (pin "P0.03") (pinfunction "P0.03_P0.03") (pintype "bidirectional"))
      (node (ref "U$19") (pin "2") (pinfunction "1_2") (pintype "bidirectional"))
      (node (ref "U$33") (pin "2") (pinfunction "1_2") (pintype "bidirectional"))
      (node (ref "U$46") (pin "2") (pinfunction "1_2") (pintype "bidirectional"))
      (node (ref "U$5") (pin "2") (pinfunction "1_2") (pintype "bidirectional"))
    )
    (net (code "8") (name "/COL6") (class "Default")
      (node (ref "IC3") (pin "P0.02") (pinfunction "P0.02_P0.02") (pintype "bidirectional"))
      (node (ref "U$20") (pin "2") (pinfunction "1_2") (pintype "bidirectional"))
      (node (ref "U$34") (pin "2") (pinfunction "1_2") (pintype "bidirectional"))
      (node (ref "U$47") (pin "2") (pinfunction "1_2") (pintype "bidirectional"))
      (node (ref "U$57") (pin "2") (pinfunction "1_2") (pintype "bidirectional"))
      (node (ref "U$6") (pin "2") (pinfunction "1_2") (pintype "bidirectional"))
    )
    (net (code "9") (name "/COL7") (class "Default")
      (node (ref "IC3") (pin "P0.28") (pinfunction "P0.28_P0.28") (pintype "bidirectional"))
      (node (ref "U$21") (pin "2") (pinfunction "1_2") (pintype "bidirectional"))
      (node (ref "U$35") (pin "2") (pinfunction "1_2") (pintype "bidirectional"))
      (node (ref "U$48") (pin "2") (pinfunction "1_2") (pintype "bidirectional"))
      (node (ref "U$7") (pin "2") (pinfunction "1_2") (pintype "bidirectional"))
    )
    (net (code "10") (name "/COL8") (class "Default")
      (node (ref "IC3") (pin "P0.29") (pinfunction "P0.29_P0.29") (pintype "bidirectional"))
      (node (ref "U$22") (pin "2") (pinfunction "1_2") (pintype "bidirectional"))
      (node (ref "U$36") (pin "2") (pinfunction "1_2") (pintype "bidirectional"))
      (node (ref "U$49") (pin "2") (pinfunction "1_2") (pintype "bidirectional"))
      (node (ref "U$8") (pin "2") (pinfunction "1_2") (pintype "bidirectional"))
    )
    (net (code "11") (name "/COL9") (class "Default")
      (node (ref "IC3") (pin "P0.30") (pinfunction "P0.30_P0.30") (pintype "bidirectional"))
      (node (ref "U$23") (pin "2") (pinfunction "1_2") (pintype "bidirectional"))
      (node (ref "U$37") (pin "2") (pinfunction "1_2") (pintype "bidirectional"))
      (node (ref "U$50") (pin "2") (pinfunction "1_2") (pintype "bidirectional"))
      (node (ref "U$58") (pin "2") (pinfunction "1_2") (pintype "bidirectional"))
      (node (ref "U$9") (pin "2") (pinfunction "1_2") (pintype "bidirectional"))
    )
    (net (code "12") (name "/COL10") (class "Default")
      (node (ref "IC3") (pin "P0.31") (pinfunction "P0.31_P0.31") (pintype "bidirectional"))
      (node (ref "U$10") (pin "2") (pinfunction "1_2") (pintype "bidirectional"))
      (node (ref "U$24") (pin "2") (pinfunction "1_2") (pintype "bidirectional"))
      (node (ref "U$38") (pin "2") (pinfunction "1_2") (pintype "bidirectional"))
      (node (ref "U$51") (pin "2") (pinfunction "1_2") (pintype "bidirectional"))
      (node (ref "U$59") (pin "2") (pinfunction "1_2") (pintype "bidirectional"))
    )
    (net (code "13") (name "/COL11") (class "Default")
      (node (ref "IC3") (pin "P0.05") (pinfunction "P0.05_P0.05") (pintype "bidirectional"))
      (node (ref "U$11") (pin "2") (pinfunction "1_2") (pintype "bidirectional"))
      (node (ref "U$25") (pin "2") (pinfunction "1_2") (pintype "bidirectional"))
      (node (ref "U$39") (pin "2") (pinfunction "1_2") (pintype "bidirectional"))
      (node (ref "U$52") (pin "2") (pinfunction "1_2") (pintype "bidirectional"))
      (node (ref "U$60") (pin "2") (pinfunction "1_2") (pintype "bidirectional"))
    )
    (net (code "14") (name "/COL12") (class "Default")
      (node (ref "IC3") (pin "P0.07") (pinfunction "P0.07_P0.07") (pintype "bidirectional"))
      (node (ref "U$12") (pin "2") (pinfunction "1_2") (pintype "bidirectional"))
      (node (ref "U$26") (pin "2") (pinfunction "1_2") (pintype "bidirectional"))
      (node (ref "U$40") (pin "2") (pinfunction "1_2") (pintype "bidirectional"))
      (node (ref "U$53") (pin "2") (pinfunction "1_2") (pintype "bidirectional"))
      (node (ref "U$61") (pin "2") (pinfunction "1_2") (pintype "bidirectional"))
    )
    (net (code "15") (name "/COL13") (class "Default")
      (node (ref "IC3") (pin "P1.09") (pinfunction "P1.09_P1.09") (pintype "bidirectional"))
      (node (ref "U$13") (pin "2") (pinfunction "1_2") (pintype "bidirectional"))
      (node (ref "U$27") (pin "2") (pinfunction "1_2") (pintype "bidirectional"))
      (node (ref "U$41") (pin "2") (pinfunction "1_2") (pintype "bidirectional"))
    )
    (net (code "16") (name "/COL14") (class "Default")
      (node (ref "IC3") (pin "P0.12") (pinfunction "P0.12_P0.12") (pintype "bidirectional"))
      (node (ref "U$14") (pin "2") (pinfunction "1_2") (pintype "bidirectional"))
      (node (ref "U$28") (pin "2") (pinfunction "1_2") (pintype "bidirectional"))
      (node (ref "U$73") (pin "P$2") (pinfunction "1_P$2") (pintype "bidirectional"))
      (node (ref "U$74") (pin "P$2") (pinfunction "1_P$2") (pintype "bidirectional"))
    )
    (net (code "17") (name "/D+") (class "Default")
      (node (ref "D64") (pin "A") (pinfunction "A_A") (pintype "passive"))
      (node (ref "IC3") (pin "D+") (pinfunction "D+_D+") (pintype "bidirectional"))
      (node (ref "J2") (pin "3") (pinfunction "3_3") (pintype "passive"))
      (node (ref "J3") (pin "A6") (pinfunction "D+_A6") (pintype "bidirectional"))
      (node (ref "J3") (pin "B6") (pinfunction "D+_B6") (pintype "bidirectional"))
    )
    (net (code "18") (name "/D-") (class "Default")
      (node (ref "D65") (pin "A") (pinfunction "A_A") (pintype "passive"))
      (node (ref "IC3") (pin "D-") (pinfunction "D-_D-") (pintype "bidirectional"))
      (node (ref "J2") (pin "2") (pinfunction "2_2") (pintype "passive"))
      (node (ref "J3") (pin "A7") (pinfunction "D-_A7") (pintype "bidirectional"))
      (node (ref "J3") (pin "B7") (pinfunction "D-_B7") (pintype "bidirectional"))
    )
    (net (code "19") (name "/G_BAT") (class "Default")
      (node (ref "C5") (pin "2") (pinfunction "2_2") (pintype "passive"))
      (node (ref "CN2") (pin "1") (pinfunction "1_1") (pintype "passive"))
      (node (ref "IC1") (pin "3") (pinfunction "GND_3") (pintype "bidirectional"))
      (node (ref "J4") (pin "2") (pinfunction "2_2") (pintype "passive"))
    )
    (net (code "20") (name "/POWER_PIN") (class "Default")
      (node (ref "IC3") (pin "P0.13") (pinfunction "P0.13_P0.13") (pintype "bidirectional"))
    )
    (net (code "21") (name "/RESET") (class "Default")
      (node (ref "IC3") (pin "P0.14") (pinfunction "P0.14_P0.14") (pintype "bidirectional"))
      (node (ref "IC3") (pin "P0.16") (pinfunction "P0.16_P0.16") (pintype "bidirectional"))
      (node (ref "IC3") (pin "P0.18") (pinfunction "P0.18_P0.18") (pintype "bidirectional"))
      (node (ref "PROG1") (pin "3") (pinfunction "3_3") (pintype "passive"))
      (node (ref "R2") (pin "2") (pinfunction "2_2") (pintype "passive"))
      (node (ref "U$62") (pin "C") (pinfunction "C_C") (pintype "bidirectional"))
      (node (ref "U$62") (pin "D") (pinfunction "D_D") (pintype "bidirectional"))
    )
    (net (code "22") (name "/ROW1") (class "Default")
      (node (ref "D1") (pin "C") (pinfunction "C_C") (pintype "passive"))
      (node (ref "D10") (pin "C") (pinfunction "C_C") (pintype "passive"))
      (node (ref "D11") (pin "C") (pinfunction "C_C") (pintype "passive"))
      (node (ref "D12") (pin "C") (pinfunction "C_C") (pintype "passive"))
      (node (ref "D13") (pin "C") (pinfunction "C_C") (pintype "passive"))
      (node (ref "D14") (pin "C") (pinfunction "C_C") (pintype "passive"))
      (node (ref "D2") (pin "C") (pinfunction "C_C") (pintype "passive"))
      (node (ref "D3") (pin "C") (pinfunction "C_C") (pintype "passive"))
      (node (ref "D4") (pin "C") (pinfunction "C_C") (pintype "passive"))
      (node (ref "D5") (pin "C") (pinfunction "C_C") (pintype "passive"))
      (node (ref "D6") (pin "C") (pinfunction "C_C") (pintype "passive"))
      (node (ref "D7") (pin "C") (pinfunction "C_C") (pintype "passive"))
      (node (ref "D8") (pin "C") (pinfunction "C_C") (pintype "passive"))
      (node (ref "D9") (pin "C") (pinfunction "C_C") (pintype "passive"))
      (node (ref "IC3") (pin "P1.00") (pinfunction "P1.00_P1.00") (pintype "bidirectional"))
    )
    (net (code "23") (name "/ROW2") (class "Default")
      (node (ref "D15") (pin "C") (pinfunction "C_C") (pintype "passive"))
      (node (ref "D16") (pin "C") (pinfunction "C_C") (pintype "passive"))
      (node (ref "D17") (pin "C") (pinfunction "C_C") (pintype "passive"))
      (node (ref "D18") (pin "C") (pinfunction "C_C") (pintype "passive"))
      (node (ref "D19") (pin "C") (pinfunction "C_C") (pintype "passive"))
      (node (ref "D20") (pin "C") (pinfunction "C_C") (pintype "passive"))
      (node (ref "D21") (pin "C") (pinfunction "C_C") (pintype "passive"))
      (node (ref "D22") (pin "C") (pinfunction "C_C") (pintype "passive"))
      (node (ref "D23") (pin "C") (pinfunction "C_C") (pintype "passive"))
      (node (ref "D24") (pin "C") (pinfunction "C_C") (pintype "passive"))
      (node (ref "D25") (pin "C") (pinfunction "C_C") (pintype "passive"))
      (node (ref "D26") (pin "C") (pinfunction "C_C") (pintype "passive"))
      (node (ref "D27") (pin "C") (pinfunction "C_C") (pintype "passive"))
      (node (ref "D28") (pin "C") (pinfunction "C_C") (pintype "passive"))
      (node (ref "IC3") (pin "P0.22") (pinfunction "P0.22_P0.22") (pintype "bidirectional"))
    )
    (net (code "24") (name "/ROW3") (class "Default")
      (node (ref "D29") (pin "C") (pinfunction "C_C") (pintype "passive"))
      (node (ref "D30") (pin "C") (pinfunction "C_C") (pintype "passive"))
      (node (ref "D31") (pin "C") (pinfunction "C_C") (pintype "passive"))
      (node (ref "D32") (pin "C") (pinfunction "C_C") (pintype "passive"))
      (node (ref "D33") (pin "C") (pinfunction "C_C") (pintype "passive"))
      (node (ref "D34") (pin "C") (pinfunction "C_C") (pintype "passive"))
      (node (ref "D35") (pin "C") (pinfunction "C_C") (pintype "passive"))
      (node (ref "D36") (pin "C") (pinfunction "C_C") (pintype "passive"))
      (node (ref "D37") (pin "C") (pinfunction "C_C") (pintype "passive"))
      (node (ref "D38") (pin "C") (pinfunction "C_C") (pintype "passive"))
      (node (ref "D39") (pin "C") (pinfunction "C_C") (pintype "passive"))
      (node (ref "D40") (pin "C") (pinfunction "C_C") (pintype "passive"))
      (node (ref "D41") (pin "C") (pinfunction "C_C") (pintype "passive"))
      (node (ref "D62") (pin "C") (pinfunction "C_C") (pintype "passive"))
      (node (ref "IC3") (pin "P0.19") (pinfunction "P0.19_P0.19") (pintype "bidirectional"))
    )
    (net (code "25") (name "/ROW4") (class "Default")
      (node (ref "D42") (pin "C") (pinfunction "C_C") (pintype "passive"))
      (node (ref "D43") (pin "C") (pinfunction "C_C") (pintype "passive"))
      (node (ref "D44") (pin "C") (pinfunction "C_C") (pintype "passive"))
      (node (ref "D45") (pin "C") (pinfunction "C_C") (pintype "passive"))
      (node (ref "D46") (pin "C") (pinfunction "C_C") (pintype "passive"))
      (node (ref "D47") (pin "C") (pinfunction "C_C") (pintype "passive"))
      (node (ref "D48") (pin "C") (pinfunction "C_C") (pintype "passive"))
      (node (ref "D49") (pin "C") (pinfunction "C_C") (pintype "passive"))
      (node (ref "D50") (pin "C") (pinfunction "C_C") (pintype "passive"))
      (node (ref "D51") (pin "C") (pinfunction "C_C") (pintype "passive"))
      (node (ref "D52") (pin "C") (pinfunction "C_C") (pintype "passive"))
      (node (ref "D53") (pin "C") (pinfunction "C_C") (pintype "passive"))
      (node (ref "IC3") (pin "P0.21") (pinfunction "P0.21_P0.21") (pintype "bidirectional"))
    )
    (net (code "26") (name "/ROW5") (class "Default")
      (node (ref "D54") (pin "C") (pinfunction "C_C") (pintype "passive"))
      (node (ref "D55") (pin "C") (pinfunction "C_C") (pintype "passive"))
      (node (ref "D56") (pin "C") (pinfunction "C_C") (pintype "passive"))
      (node (ref "D57") (pin "C") (pinfunction "C_C") (pintype "passive"))
      (node (ref "D58") (pin "C") (pinfunction "C_C") (pintype "passive"))
      (node (ref "D59") (pin "C") (pinfunction "C_C") (pintype "passive"))
      (node (ref "D60") (pin "C") (pinfunction "C_C") (pintype "passive"))
      (node (ref "D61") (pin "C") (pinfunction "C_C") (pintype "passive"))
      (node (ref "IC3") (pin "P0.23") (pinfunction "P0.23_P0.23") (pintype "bidirectional"))
    )
    (net (code "27") (name "/RXD") (class "Default")
      (node (ref "IC3") (pin "P0.08") (pinfunction "P0.08_P0.08") (pintype "bidirectional"))
    )
    (net (code "28") (name "/SCK") (class "Default")
      (node (ref "IC3") (pin "SWDCLK") (pinfunction "SWDCLK_SWDCLK") (pintype "bidirectional"))
      (node (ref "PROG1") (pin "4") (pinfunction "4_4") (pintype "passive"))
    )
    (net (code "29") (name "/SWD") (class "Default")
      (node (ref "IC3") (pin "SWDIO") (pinfunction "SWDIO_SWDIO") (pintype "bidirectional"))
      (node (ref "PROG1") (pin "5") (pinfunction "5_5") (pintype "passive"))
    )
    (net (code "30") (name "/TXD") (class "Default")
      (node (ref "IC3") (pin "P0.06") (pinfunction "P0.06_P0.06") (pintype "bidirectional"))
    )
    (net (code "31") (name "/VDD_NRF") (class "Default")
      (node (ref "D66") (pin "A") (pinfunction "A_A") (pintype "passive"))
      (node (ref "IC3") (pin "VDD_NRF") (pinfunction "VDD_NRF_VDD_NRF") (pintype "bidirectional"))
      (node (ref "PROG1") (pin "1") (pinfunction "1_1") (pintype "passive"))
      (node (ref "R2") (pin "1") (pinfunction "1_1") (pintype "passive"))
      (node (ref "U2") (pin "5") (pinfunction "VOUT_5") (pintype "power_in"))
    )
    (net (code "32") (name "GND") (class "Default")
      (node (ref "C4") (pin "2") (pinfunction "2_2") (pintype "passive"))
      (node (ref "C6") (pin "2") (pinfunction "2_2") (pintype "passive"))
      (node (ref "D64") (pin "C") (pinfunction "C_C") (pintype "passive"))
      (node (ref "D65") (pin "C") (pinfunction "C_C") (pintype "passive"))
      (node (ref "D66") (pin "C") (pinfunction "C_C") (pintype "passive"))
      (node (ref "D67") (pin "C") (pinfunction "C_C") (pintype "passive"))
      (node (ref "IC1") (pin "1") (pinfunction "VM_1") (pintype "bidirectional"))
      (node (ref "IC3") (pin "GND") (pinfunction "GND1_GND") (pintype "bidirectional"))
      (node (ref "IC3") (pin "GND1") (pinfunction "GND2_GND1") (pintype "bidirectional"))
      (node (ref "IC3") (pin "GND2") (pinfunction "GND3_GND2") (pintype "bidirectional"))
      (node (ref "J2") (pin "4") (pinfunction "4_4") (pintype "passive"))
      (node (ref "J3") (pin "GND") (pinfunction "GND_GND") (pintype "bidirectional"))
      (node (ref "J3") (pin "GND2") (pinfunction "GND_GND2") (pintype "bidirectional"))
      (node (ref "J3") (pin "SHLD1") (pinfunction "SHLD_SHLD1") (pintype "bidirectional"))
      (node (ref "J3") (pin "SHLD2") (pinfunction "SHLD_SHLD2") (pintype "bidirectional"))
      (node (ref "J3") (pin "SHLD3") (pinfunction "SHLD_SHLD3") (pintype "bidirectional"))
      (node (ref "J3") (pin "SHLD4") (pinfunction "SHLD_SHLD4") (pintype "bidirectional"))
      (node (ref "J3") (pin "SHLD5") (pinfunction "SHLD_SHLD5") (pintype "bidirectional"))
      (node (ref "J3") (pin "SHLD6") (pinfunction "SHLD_SHLD6") (pintype "bidirectional"))
      (node (ref "J3") (pin "SHLD7") (pinfunction "SHLD_SHLD7") (pintype "bidirectional"))
      (node (ref "J3") (pin "SHLD8") (pinfunction "SHLD_SHLD8") (pintype "bidirectional"))
      (node (ref "PROG1") (pin "2") (pinfunction "2_2") (pintype "passive"))
      (node (ref "R1") (pin "1") (pinfunction "1_1") (pintype "passive"))
      (node (ref "R11") (pin "1") (pinfunction "1_1") (pintype "passive"))
      (node (ref "R12") (pin "1") (pinfunction "1_1") (pintype "passive"))
      (node (ref "R13") (pin "1") (pinfunction "1_1") (pintype "passive"))
      (node (ref "R17") (pin "1") (pinfunction "1_1") (pintype "passive"))
      (node (ref "R20") (pin "2") (pinfunction "2_2") (pintype "passive"))
      (node (ref "U$62") (pin "A") (pinfunction "A_A") (pintype "bidirectional"))
      (node (ref "U$62") (pin "B") (pinfunction "B_B") (pintype "bidirectional"))
      (node (ref "U$63") (pin "1") (pinfunction "TEMP_1") (pintype "bidirectional"))
      (node (ref "U$63") (pin "3") (pinfunction "GND_3") (pintype "bidirectional"))
      (node (ref "U$64") (pin "P$1") (pinfunction "P$1_P$1") (pintype "bidirectional"))
      (node (ref "U$64") (pin "P$2") (pinfunction "P$1_P$2") (pintype "bidirectional"))
      (node (ref "U$65") (pin "P$1") (pinfunction "P$1_P$1") (pintype "bidirectional"))
      (node (ref "U$65") (pin "P$2") (pinfunction "P$1_P$2") (pintype "bidirectional"))
      (node (ref "U$66") (pin "P$1") (pinfunction "P$1_P$1") (pintype "bidirectional"))
      (node (ref "U$66") (pin "P$2") (pinfunction "P$1_P$2") (pintype "bidirectional"))
      (node (ref "U$67") (pin "P$1") (pinfunction "P$1_P$1") (pintype "bidirectional"))
      (node (ref "U$67") (pin "P$2") (pinfunction "P$1_P$2") (pintype "bidirectional"))
      (node (ref "U2") (pin "2") (pinfunction "GND_2") (pintype "power_in"))
    )
    (net (code "33") (name "Net-(D63-K)") (class "Default")
      (node (ref "C6") (pin "1") (pinfunction "1_1") (pintype "passive"))
      (node (ref "D63") (pin "1") (pinfunction "K_1") (pintype "bidirectional"))
      (node (ref "Q5") (pin "2") (pinfunction "S_2") (pintype "passive"))
      (node (ref "U2") (pin "1") (pinfunction "VIN_1") (pintype "power_in"))
      (node (ref "U2") (pin "3") (pinfunction "EN_3") (pintype "input"))
    )
    (net (code "34") (name "Net-(FUSE-Pad2)") (class "Default")
      (node (ref "FUSE") (pin "2") (pinfunction "2_2") (pintype "passive"))
      (node (ref "J3") (pin "VBUS1") (pinfunction "VBUS_VBUS1") (pintype "bidirectional"))
      (node (ref "J3") (pin "VBUS2") (pinfunction "VBUS_VBUS2") (pintype "bidirectional"))
    )
    (net (code "35") (name "Net-(IC1-VDD)") (class "Default")
      (node (ref "C5") (pin "1") (pinfunction "1_1") (pintype "passive"))
      (node (ref "IC1") (pin "2") (pinfunction "VDD_2") (pintype "bidirectional"))
      (node (ref "R15") (pin "1") (pinfunction "1_1") (pintype "passive"))
    )
    (net (code "36") (name "Net-(IC3-PadP0.17)") (class "Default")
      (node (ref "IC3") (pin "P0.17") (pinfunction "P0.17_P0.17") (pintype "bidirectional"))
      (node (ref "J1") (pin "5") (pinfunction "5_5") (pintype "passive"))
    )
    (net (code "37") (name "Net-(IC3-PadP0.20)") (class "Default")
      (node (ref "IC3") (pin "P0.20") (pinfunction "P0.20_P0.20") (pintype "bidirectional"))
      (node (ref "J1") (pin "4") (pinfunction "4_4") (pintype "passive"))
    )
    (net (code "38") (name "Net-(IC3-PadP0.24)") (class "Default")
      (node (ref "IC3") (pin "P0.24") (pinfunction "P0.24_P0.24") (pintype "bidirectional"))
      (node (ref "J1") (pin "3") (pinfunction "3_3") (pintype "passive"))
    )
    (net (code "39") (name "Net-(IC3-PadP1.05)") (class "Default")
      (node (ref "IC3") (pin "P1.05") (pinfunction "P1.05_P1.05") (pintype "bidirectional"))
      (node (ref "J1") (pin "2") (pinfunction "2_2") (pintype "passive"))
    )
    (net (code "40") (name "Net-(IC3-PadP1.07)") (class "Default")
      (node (ref "IC3") (pin "P1.07") (pinfunction "P1.07_P1.07") (pintype "bidirectional"))
      (node (ref "J1") (pin "1") (pinfunction "1_1") (pintype "passive"))
    )
    (net (code "41") (name "Net-(J3-CC1)") (class "Default")
      (node (ref "J3") (pin "A5") (pinfunction "CC1_A5") (pintype "bidirectional"))
      (node (ref "R12") (pin "2") (pinfunction "2_2") (pintype "passive"))
    )
    (net (code "42") (name "Net-(J3-CC2)") (class "Default")
      (node (ref "J3") (pin "B5") (pinfunction "CC2_B5") (pintype "bidirectional"))
      (node (ref "R11") (pin "2") (pinfunction "2_2") (pintype "passive"))
    )
    (net (code "43") (name "Net-(LED1-PadC)") (class "Default")
      (node (ref "LED1") (pin "C") (pinfunction "C_C") (pintype "passive"))
      (node (ref "R1") (pin "2") (pinfunction "2_2") (pintype "passive"))
    )
    (net (code "44") (name "Net-(LED2-PadC)") (class "Default")
      (node (ref "LED2") (pin "C") (pinfunction "C_C") (pintype "passive"))
      (node (ref "R14") (pin "1") (pinfunction "1_1") (pintype "passive"))
    )
    (net (code "45") (name "Net-(U$1-2)") (class "Default")
      (node (ref "D1") (pin "A") (pinfunction "A_A") (pintype "passive"))
      (node (ref "U$1") (pin "1") (pinfunction "2_1") (pintype "bidirectional"))
    )
    (net (code "46") (name "Net-(U$2-2)") (class "Default")
      (node (ref "D2") (pin "A") (pinfunction "A_A") (pintype "passive"))
      (node (ref "U$2") (pin "1") (pinfunction "2_1") (pintype "bidirectional"))
    )
    (net (code "47") (name "Net-(U$3-2)") (class "Default")
      (node (ref "D3") (pin "A") (pinfunction "A_A") (pintype "passive"))
      (node (ref "U$3") (pin "1") (pinfunction "2_1") (pintype "bidirectional"))
    )
    (net (code "48") (name "Net-(U$4-2)") (class "Default")
      (node (ref "D4") (pin "A") (pinfunction "A_A") (pintype "passive"))
      (node (ref "U$4") (pin "1") (pinfunction "2_1") (pintype "bidirectional"))
    )
    (net (code "49") (name "Net-(U$5-2)") (class "Default")
      (node (ref "D5") (pin "A") (pinfunction "A_A") (pintype "passive"))
      (node (ref "U$5") (pin "1") (pinfunction "2_1") (pintype "bidirectional"))
    )
    (net (code "50") (name "Net-(U$6-2)") (class "Default")
      (node (ref "D6") (pin "A") (pinfunction "A_A") (pintype "passive"))
      (node (ref "U$6") (pin "1") (pinfunction "2_1") (pintype "bidirectional"))
    )
    (net (code "51") (name "Net-(U$7-2)") (class "Default")
      (node (ref "D7") (pin "A") (pinfunction "A_A") (pintype "passive"))
      (node (ref "U$7") (pin "1") (pinfunction "2_1") (pintype "bidirectional"))
    )
    (net (code "52") (name "Net-(U$8-2)") (class "Default")
      (node (ref "D8") (pin "A") (pinfunction "A_A") (pintype "passive"))
      (node (ref "U$8") (pin "1") (pinfunction "2_1") (pintype "bidirectional"))
    )
    (net (code "53") (name "Net-(U$9-2)") (class "Default")
      (node (ref "D9") (pin "A") (pinfunction "A_A") (pintype "passive"))
      (node (ref "U$9") (pin "1") (pinfunction "2_1") (pintype "bidirectional"))
    )
    (net (code "54") (name "Net-(U$10-2)") (class "Default")
      (node (ref "D10") (pin "A") (pinfunction "A_A") (pintype "passive"))
      (node (ref "U$10") (pin "1") (pinfunction "2_1") (pintype "bidirectional"))
    )
    (net (code "55") (name "Net-(U$11-2)") (class "Default")
      (node (ref "D11") (pin "A") (pinfunction "A_A") (pintype "passive"))
      (node (ref "U$11") (pin "1") (pinfunction "2_1") (pintype "bidirectional"))
    )
    (net (code "56") (name "Net-(U$12-2)") (class "Default")
      (node (ref "D12") (pin "A") (pinfunction "A_A") (pintype "passive"))
      (node (ref "U$12") (pin "1") (pinfunction "2_1") (pintype "bidirectional"))
    )
    (net (code "57") (name "Net-(U$13-2)") (class "Default")
      (node (ref "D13") (pin "A") (pinfunction "A_A") (pintype "passive"))
      (node (ref "U$13") (pin "1") (pinfunction "2_1") (pintype "bidirectional"))
    )
    (net (code "58") (name "Net-(U$14-2)") (class "Default")
      (node (ref "D14") (pin "A") (pinfunction "A_A") (pintype "passive"))
      (node (ref "U$14") (pin "1") (pinfunction "2_1") (pintype "bidirectional"))
      (node (ref "U$73") (pin "P$1") (pinfunction "2_P$1") (pintype "bidirectional"))
    )
    (net (code "59") (name "Net-(U$15-2)") (class "Default")
      (node (ref "D15") (pin "A") (pinfunction "A_A") (pintype "passive"))
      (node (ref "U$15") (pin "1") (pinfunction "2_1") (pintype "bidirectional"))
    )
    (net (code "60") (name "Net-(U$16-2)") (class "Default")
      (node (ref "D16") (pin "A") (pinfunction "A_A") (pintype "passive"))
      (node (ref "U$16") (pin "1") (pinfunction "2_1") (pintype "bidirectional"))
    )
    (net (code "61") (name "Net-(U$17-2)") (class "Default")
      (node (ref "D17") (pin "A") (pinfunction "A_A") (pintype "passive"))
      (node (ref "U$17") (pin "1") (pinfunction "2_1") (pintype "bidirectional"))
    )
    (net (code "62") (name "Net-(U$18-2)") (class "Default")
      (node (ref "D18") (pin "A") (pinfunction "A_A") (pintype "passive"))
      (node (ref "U$18") (pin "1") (pinfunction "2_1") (pintype "bidirectional"))
    )
    (net (code "63") (name "Net-(U$19-2)") (class "Default")
      (node (ref "D19") (pin "A") (pinfunction "A_A") (pintype "passive"))
      (node (ref "U$19") (pin "1") (pinfunction "2_1") (pintype "bidirectional"))
    )
    (net (code "64") (name "Net-(U$20-2)") (class "Default")
      (node (ref "D20") (pin "A") (pinfunction "A_A") (pintype "passive"))
      (node (ref "U$20") (pin "1") (pinfunction "2_1") (pintype "bidirectional"))
    )
    (net (code "65") (name "Net-(U$21-2)") (class "Default")
      (node (ref "D21") (pin "A") (pinfunction "A_A") (pintype "passive"))
      (node (ref "U$21") (pin "1") (pinfunction "2_1") (pintype "bidirectional"))
    )
    (net (code "66") (name "Net-(U$22-2)") (class "Default")
      (node (ref "D22") (pin "A") (pinfunction "A_A") (pintype "passive"))
      (node (ref "U$22") (pin "1") (pinfunction "2_1") (pintype "bidirectional"))
    )
    (net (code "67") (name "Net-(U$23-2)") (class "Default")
      (node (ref "D23") (pin "A") (pinfunction "A_A") (pintype "passive"))
      (node (ref "U$23") (pin "1") (pinfunction "2_1") (pintype "bidirectional"))
    )
    (net (code "68") (name "Net-(U$24-2)") (class "Default")
      (node (ref "D24") (pin "A") (pinfunction "A_A") (pintype "passive"))
      (node (ref "U$24") (pin "1") (pinfunction "2_1") (pintype "bidirectional"))
    )
    (net (code "69") (name "Net-(U$25-2)") (class "Default")
      (node (ref "D25") (pin "A") (pinfunction "A_A") (pintype "passive"))
      (node (ref "U$25") (pin "1") (pinfunction "2_1") (pintype "bidirectional"))
    )
    (net (code "70") (name "Net-(U$26-2)") (class "Default")
      (node (ref "D26") (pin "A") (pinfunction "A_A") (pintype "passive"))
      (node (ref "U$26") (pin "1") (pinfunction "2_1") (pintype "bidirectional"))
    )
    (net (code "71") (name "Net-(U$27-2)") (class "Default")
      (node (ref "D27") (pin "A") (pinfunction "A_A") (pintype "passive"))
      (node (ref "U$27") (pin "1") (pinfunction "2_1") (pintype "bidirectional"))
    )
    (net (code "72") (name "Net-(U$28-2)") (class "Default")
      (node (ref "D28") (pin "A") (pinfunction "A_A") (pintype "passive"))
      (node (ref "U$28") (pin "1") (pinfunction "2_1") (pintype "bidirectional"))
    )
    (net (code "73") (name "Net-(U$29-2)") (class "Default")
      (node (ref "D29") (pin "A") (pinfunction "A_A") (pintype "passive"))
      (node (ref "U$29") (pin "1") (pinfunction "2_1") (pintype "bidirectional"))
    )
    (net (code "74") (name "Net-(U$30-2)") (class "Default")
      (node (ref "D30") (pin "A") (pinfunction "A_A") (pintype "passive"))
      (node (ref "U$30") (pin "1") (pinfunction "2_1") (pintype "bidirectional"))
    )
    (net (code "75") (name "Net-(U$31-2)") (class "Default")
      (node (ref "D31") (pin "A") (pinfunction "A_A") (pintype "passive"))
      (node (ref "U$31") (pin "1") (pinfunction "2_1") (pintype "bidirectional"))
    )
    (net (code "76") (name "Net-(U$32-2)") (class "Default")
      (node (ref "D32") (pin "A") (pinfunction "A_A") (pintype "passive"))
      (node (ref "U$32") (pin "1") (pinfunction "2_1") (pintype "bidirectional"))
    )
    (net (code "77") (name "Net-(U$33-2)") (class "Default")
      (node (ref "D33") (pin "A") (pinfunction "A_A") (pintype "passive"))
      (node (ref "U$33") (pin "1") (pinfunction "2_1") (pintype "bidirectional"))
    )
    (net (code "78") (name "Net-(U$34-2)") (class "Default")
      (node (ref "D34") (pin "A") (pinfunction "A_A") (pintype "passive"))
      (node (ref "U$34") (pin "1") (pinfunction "2_1") (pintype "bidirectional"))
    )
    (net (code "79") (name "Net-(U$35-2)") (class "Default")
      (node (ref "D35") (pin "A") (pinfunction "A_A") (pintype "passive"))
      (node (ref "U$35") (pin "1") (pinfunction "2_1") (pintype "bidirectional"))
    )
    (net (code "80") (name "Net-(U$36-2)") (class "Default")
      (node (ref "D36") (pin "A") (pinfunction "A_A") (pintype "passive"))
      (node (ref "U$36") (pin "1") (pinfunction "2_1") (pintype "bidirectional"))
    )
    (net (code "81") (name "Net-(U$37-2)") (class "Default")
      (node (ref "D37") (pin "A") (pinfunction "A_A") (pintype "passive"))
      (node (ref "U$37") (pin "1") (pinfunction "2_1") (pintype "bidirectional"))
    )
    (net (code "82") (name "Net-(U$38-2)") (class "Default")
      (node (ref "D38") (pin "A") (pinfunction "A_A") (pintype "passive"))
      (node (ref "U$38") (pin "1") (pinfunction "2_1") (pintype "bidirectional"))
    )
    (net (code "83") (name "Net-(U$39-2)") (class "Default")
      (node (ref "D39") (pin "A") (pinfunction "A_A") (pintype "passive"))
      (node (ref "U$39") (pin "1") (pinfunction "2_1") (pintype "bidirectional"))
    )
    (net (code "84") (name "Net-(U$40-2)") (class "Default")
      (node (ref "D40") (pin "A") (pinfunction "A_A") (pintype "passive"))
      (node (ref "U$40") (pin "1") (pinfunction "2_1") (pintype "bidirectional"))
    )
    (net (code "85") (name "Net-(U$41-2)") (class "Default")
      (node (ref "D41") (pin "A") (pinfunction "A_A") (pintype "passive"))
      (node (ref "U$41") (pin "1") (pinfunction "2_1") (pintype "bidirectional"))
    )
    (net (code "86") (name "Net-(U$42-2)") (class "Default")
      (node (ref "D42") (pin "A") (pinfunction "A_A") (pintype "passive"))
      (node (ref "U$42") (pin "1") (pinfunction "2_1") (pintype "bidirectional"))
    )
    (net (code "87") (name "Net-(U$43-2)") (class "Default")
      (node (ref "D43") (pin "A") (pinfunction "A_A") (pintype "passive"))
      (node (ref "U$43") (pin "1") (pinfunction "2_1") (pintype "bidirectional"))
    )
    (net (code "88") (name "Net-(U$44-2)") (class "Default")
      (node (ref "D44") (pin "A") (pinfunction "A_A") (pintype "passive"))
      (node (ref "U$44") (pin "1") (pinfunction "2_1") (pintype "bidirectional"))
    )
    (net (code "89") (name "Net-(U$45-2)") (class "Default")
      (node (ref "D45") (pin "A") (pinfunction "A_A") (pintype "passive"))
      (node (ref "U$45") (pin "1") (pinfunction "2_1") (pintype "bidirectional"))
    )
    (net (code "90") (name "Net-(U$46-2)") (class "Default")
      (node (ref "D46") (pin "A") (pinfunction "A_A") (pintype "passive"))
      (node (ref "U$46") (pin "1") (pinfunction "2_1") (pintype "bidirectional"))
    )
    (net (code "91") (name "Net-(U$47-2)") (class "Default")
      (node (ref "D47") (pin "A") (pinfunction "A_A") (pintype "passive"))
      (node (ref "U$47") (pin "1") (pinfunction "2_1") (pintype "bidirectional"))
    )
    (net (code "92") (name "Net-(U$48-2)") (class "Default")
      (node (ref "D48") (pin "A") (pinfunction "A_A") (pintype "passive"))
      (node (ref "U$48") (pin "1") (pinfunction "2_1") (pintype "bidirectional"))
    )
    (net (code "93") (name "Net-(U$49-2)") (class "Default")
      (node (ref "D49") (pin "A") (pinfunction "A_A") (pintype "passive"))
      (node (ref "U$49") (pin "1") (pinfunction "2_1") (pintype "bidirectional"))
    )
    (net (code "94") (name "Net-(U$50-2)") (class "Default")
      (node (ref "D50") (pin "A") (pinfunction "A_A") (pintype "passive"))
      (node (ref "U$50") (pin "1") (pinfunction "2_1") (pintype "bidirectional"))
    )
    (net (code "95") (name "Net-(U$51-2)") (class "Default")
      (node (ref "D51") (pin "A") (pinfunction "A_A") (pintype "passive"))
      (node (ref "U$51") (pin "1") (pinfunction "2_1") (pintype "bidirectional"))
    )
    (net (code "96") (name "Net-(U$52-2)") (class "Default")
      (node (ref "D52") (pin "A") (pinfunction "A_A") (pintype "passive"))
      (node (ref "U$52") (pin "1") (pinfunction "2_1") (pintype "bidirectional"))
    )
    (net (code "97") (name "Net-(U$53-2)") (class "Default")
      (node (ref "D53") (pin "A") (pinfunction "A_A") (pintype "passive"))
      (node (ref "U$53") (pin "1") (pinfunction "2_1") (pintype "bidirectional"))
    )
    (net (code "98") (name "Net-(U$54-2)") (class "Default")
      (node (ref "D54") (pin "A") (pinfunction "A_A") (pintype "passive"))
      (node (ref "U$54") (pin "1") (pinfunction "2_1") (pintype "bidirectional"))
    )
    (net (code "99") (name "Net-(U$55-2)") (class "Default")
      (node (ref "D55") (pin "A") (pinfunction "A_A") (pintype "passive"))
      (node (ref "U$55") (pin "1") (pinfunction "2_1") (pintype "bidirectional"))
    )
    (net (code "100") (name "Net-(U$56-2)") (class "Default")
      (node (ref "D56") (pin "A") (pinfunction "A_A") (pintype "passive"))
      (node (ref "U$56") (pin "1") (pinfunction "2_1") (pintype "bidirectional"))
    )
    (net (code "101") (name "Net-(U$57-2)") (class "Default")
      (node (ref "D57") (pin "A") (pinfunction "A_A") (pintype "passive"))
      (node (ref "U$57") (pin "1") (pinfunction "2_1") (pintype "bidirectional"))
    )
    (net (code "102") (name "Net-(U$58-2)") (class "Default")
      (node (ref "D58") (pin "A") (pinfunction "A_A") (pintype "passive"))
      (node (ref "U$58") (pin "1") (pinfunction "2_1") (pintype "bidirectional"))
    )
    (net (code "103") (name "Net-(U$59-2)") (class "Default")
      (node (ref "D59") (pin "A") (pinfunction "A_A") (pintype "passive"))
      (node (ref "U$59") (pin "1") (pinfunction "2_1") (pintype "bidirectional"))
    )
    (net (code "104") (name "Net-(U$60-2)") (class "Default")
      (node (ref "D60") (pin "A") (pinfunction "A_A") (pintype "passive"))
      (node (ref "U$60") (pin "1") (pinfunction "2_1") (pintype "bidirectional"))
    )
    (net (code "105") (name "Net-(U$61-2)") (class "Default")
      (node (ref "D61") (pin "A") (pinfunction "A_A") (pintype "passive"))
      (node (ref "U$61") (pin "1") (pinfunction "2_1") (pintype "bidirectional"))
    )
    (net (code "106") (name "Net-(U$63-PROG)") (class "Default")
      (node (ref "R13") (pin "2") (pinfunction "2_2") (pintype "passive"))
      (node (ref "U$63") (pin "2") (pinfunction "PROG_2") (pintype "bidirectional"))
    )
    (net (code "107") (name "Net-(U$63-~{CHRG})") (class "Default")
      (node (ref "R14") (pin "2") (pinfunction "2_2") (pintype "passive"))
      (node (ref "U$63") (pin "7") (pinfunction "~{CHRG}_7") (pintype "bidirectional"))
    )
    (net (code "108") (name "Net-(U$74-2)") (class "Default")
      (node (ref "D62") (pin "A") (pinfunction "A_A") (pintype "passive"))
      (node (ref "U$74") (pin "P$1") (pinfunction "2_P$1") (pintype "bidirectional"))
    )
    (net (code "109") (name "V_BATT") (class "Default")
      (node (ref "CN2") (pin "2") (pinfunction "2_2") (pintype "passive"))
      (node (ref "J4") (pin "1") (pinfunction "1_1") (pintype "passive"))
      (node (ref "Q5") (pin "3") (pinfunction "D_3") (pintype "passive"))
      (node (ref "R15") (pin "2") (pinfunction "2_2") (pintype "passive"))
      (node (ref "R19") (pin "1") (pinfunction "1_1") (pintype "passive"))
      (node (ref "U$63") (pin "5") (pinfunction "BAT_5") (pintype "bidirectional"))
    )
    (net (code "110") (name "V_USB") (class "Default")
      (node (ref "C4") (pin "1") (pinfunction "1_1") (pintype "passive"))
      (node (ref "D63") (pin "2") (pinfunction "A_2") (pintype "bidirectional"))
      (node (ref "D67") (pin "A") (pinfunction "A_A") (pintype "passive"))
      (node (ref "FUSE") (pin "1") (pinfunction "1_1") (pintype "passive"))
      (node (ref "IC3") (pin "VBUS") (pinfunction "VBUS_VBUS") (pintype "bidirectional"))
      (node (ref "J2") (pin "1") (pinfunction "1_1") (pintype "passive"))
      (node (ref "LED2") (pin "A") (pinfunction "A_A") (pintype "passive"))
      (node (ref "PROG1") (pin "6") (pinfunction "6_6") (pintype "passive"))
      (node (ref "Q5") (pin "1") (pinfunction "G_1") (pintype "passive"))
      (node (ref "R17") (pin "2") (pinfunction "2_2") (pintype "passive"))
      (node (ref "U$63") (pin "4") (pinfunction "VCC_4") (pintype "bidirectional"))
      (node (ref "U$63") (pin "8") (pinfunction "CE_8") (pintype "bidirectional"))
    )
    (net (code "111") (name "unconnected-(D68-PadA)") (class "Default")
      (node (ref "D68") (pin "A") (pinfunction "A_A") (pintype "passive"))
    )
    (net (code "112") (name "unconnected-(D68-PadC)") (class "Default")
      (node (ref "D68") (pin "C") (pinfunction "C_C") (pintype "passive"))
    )
    (net (code "113") (name "unconnected-(D69-PadA)") (class "Default")
      (node (ref "D69") (pin "A") (pinfunction "A_A") (pintype "passive"))
    )
    (net (code "114") (name "unconnected-(D69-PadC)") (class "Default")
      (node (ref "D69") (pin "C") (pinfunction "C_C") (pintype "passive"))
    )
    (net (code "115") (name "unconnected-(D70-PadA)") (class "Default")
      (node (ref "D70") (pin "A") (pinfunction "A_A") (pintype "passive"))
    )
    (net (code "116") (name "unconnected-(D70-PadC)") (class "Default")
      (node (ref "D70") (pin "C") (pinfunction "C_C") (pintype "passive"))
    )
    (net (code "117") (name "unconnected-(D71-PadA)") (class "Default")
      (node (ref "D71") (pin "A") (pinfunction "A_A") (pintype "passive"))
    )
    (net (code "118") (name "unconnected-(D71-PadC)") (class "Default")
      (node (ref "D71") (pin "C") (pinfunction "C_C") (pintype "passive"))
    )
    (net (code "119") (name "unconnected-(IC3-PadP0.09)") (class "Default")
      (node (ref "IC3") (pin "P0.09") (pinfunction "P0.09_P0.09") (pintype "bidirectional"))
    )
    (net (code "120") (name "unconnected-(IC3-PadP0.10)") (class "Default")
      (node (ref "IC3") (pin "P0.10") (pinfunction "P0.10_P0.10") (pintype "bidirectional"))
    )
    (net (code "121") (name "unconnected-(IC3-PadP0.11)") (class "Default")
      (node (ref "IC3") (pin "P0.11") (pinfunction "P0.11_P0.11") (pintype "bidirectional"))
    )
    (net (code "122") (name "unconnected-(IC3-PadP0.25)") (class "Default")
      (node (ref "IC3") (pin "P0.25") (pinfunction "P0.25_P0.25") (pintype "bidirectional"))
    )
    (net (code "123") (name "unconnected-(IC3-PadP0.26)") (class "Default")
      (node (ref "IC3") (pin "P0.26") (pinfunction "P0.26_P0.26") (pintype "bidirectional"))
    )
    (net (code "124") (name "unconnected-(IC3-PadP0.27)") (class "Default")
      (node (ref "IC3") (pin "P0.27") (pinfunction "P0.27_P0.27") (pintype "bidirectional"))
    )
    (net (code "125") (name "unconnected-(IC3-PadP1.01)") (class "Default")
      (node (ref "IC3") (pin "P1.01") (pinfunction "P1.01_P1.01") (pintype "bidirectional"))
    )
    (net (code "126") (name "unconnected-(IC3-PadP1.02)") (class "Default")
      (node (ref "IC3") (pin "P1.02") (pinfunction "P1.02_P1.02") (pintype "bidirectional"))
    )
    (net (code "127") (name "unconnected-(IC3-PadP1.03)") (class "Default")
      (node (ref "IC3") (pin "P1.03") (pinfunction "P1.03_P1.03") (pintype "bidirectional"))
    )
    (net (code "128") (name "unconnected-(IC3-PadP1.04)") (class "Default")
      (node (ref "IC3") (pin "P1.04") (pinfunction "P1.04_P1.04") (pintype "bidirectional"))
    )
    (net (code "129") (name "unconnected-(IC3-PadP1.06)") (class "Default")
      (node (ref "IC3") (pin "P1.06") (pinfunction "P1.06_P1.06") (pintype "bidirectional"))
    )
    (net (code "130") (name "unconnected-(IC3-PadP1.08)") (class "Default")
      (node (ref "IC3") (pin "P1.08") (pinfunction "P1.08_P1.08") (pintype "bidirectional"))
    )
    (net (code "131") (name "unconnected-(IC3-PadP1.12)") (class "Default")
      (node (ref "IC3") (pin "P1.12") (pinfunction "P1.12_P1.12") (pintype "bidirectional"))
    )
    (net (code "132") (name "unconnected-(IC3-PadP1.14)") (class "Default")
      (node (ref "IC3") (pin "P1.14") (pinfunction "P1.14_P1.14") (pintype "bidirectional"))
    )
    (net (code "133") (name "unconnected-(U$63-~{STDBY}-Pad6)") (class "Default")
      (node (ref "U$63") (pin "6") (pinfunction "~{STDBY}_6") (pintype "bidirectional"))
    )
  )
)
